# mainboard_2l.net
KiCad netlist of a schematic drawn in EAGLE
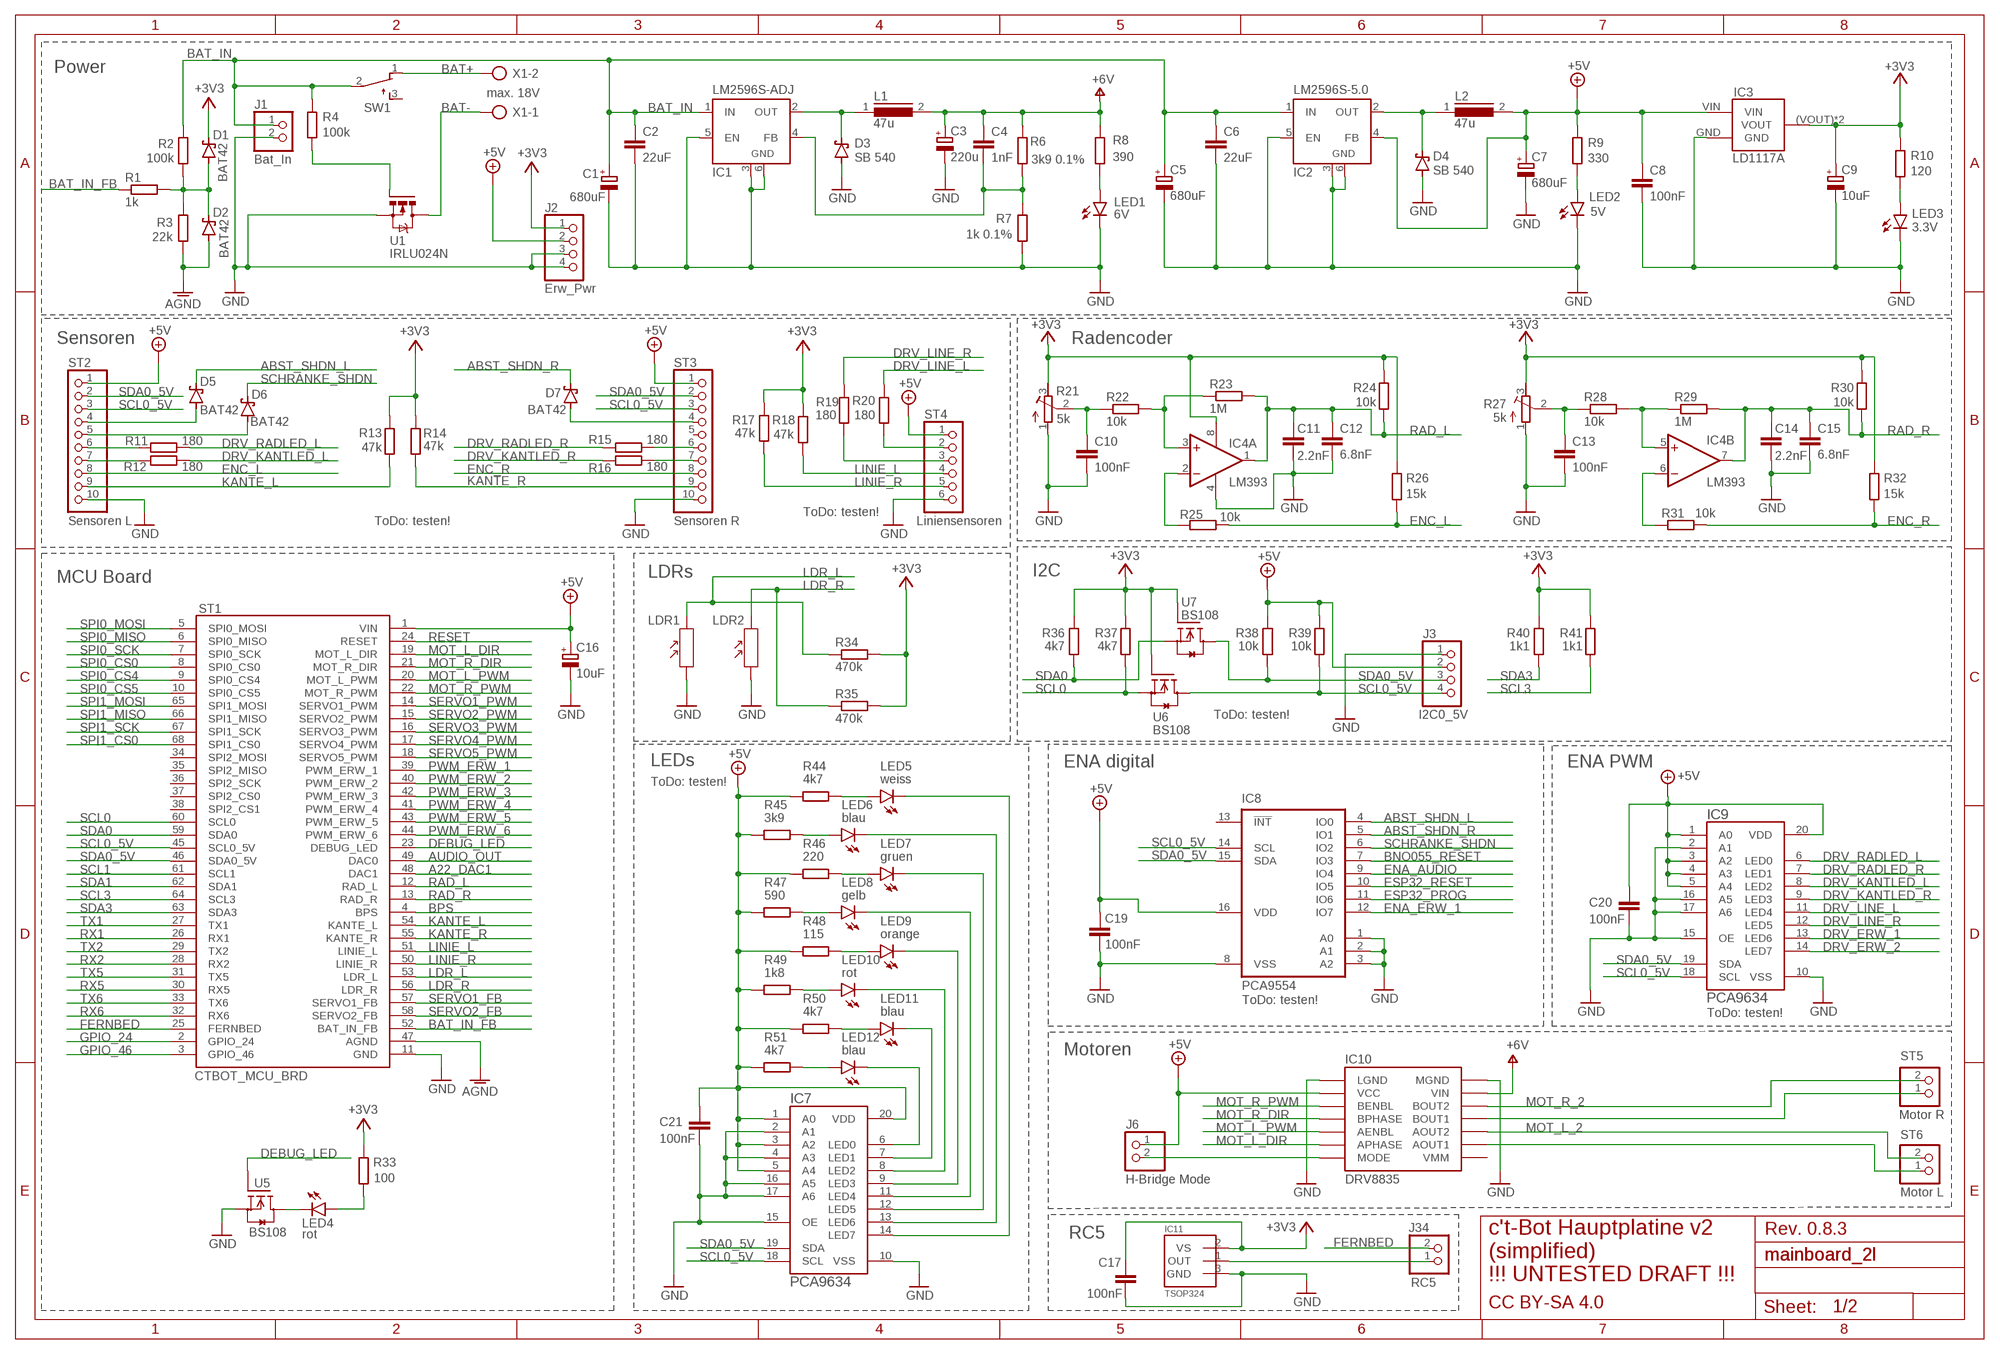
[diagram p0: schematic, sheet 1]
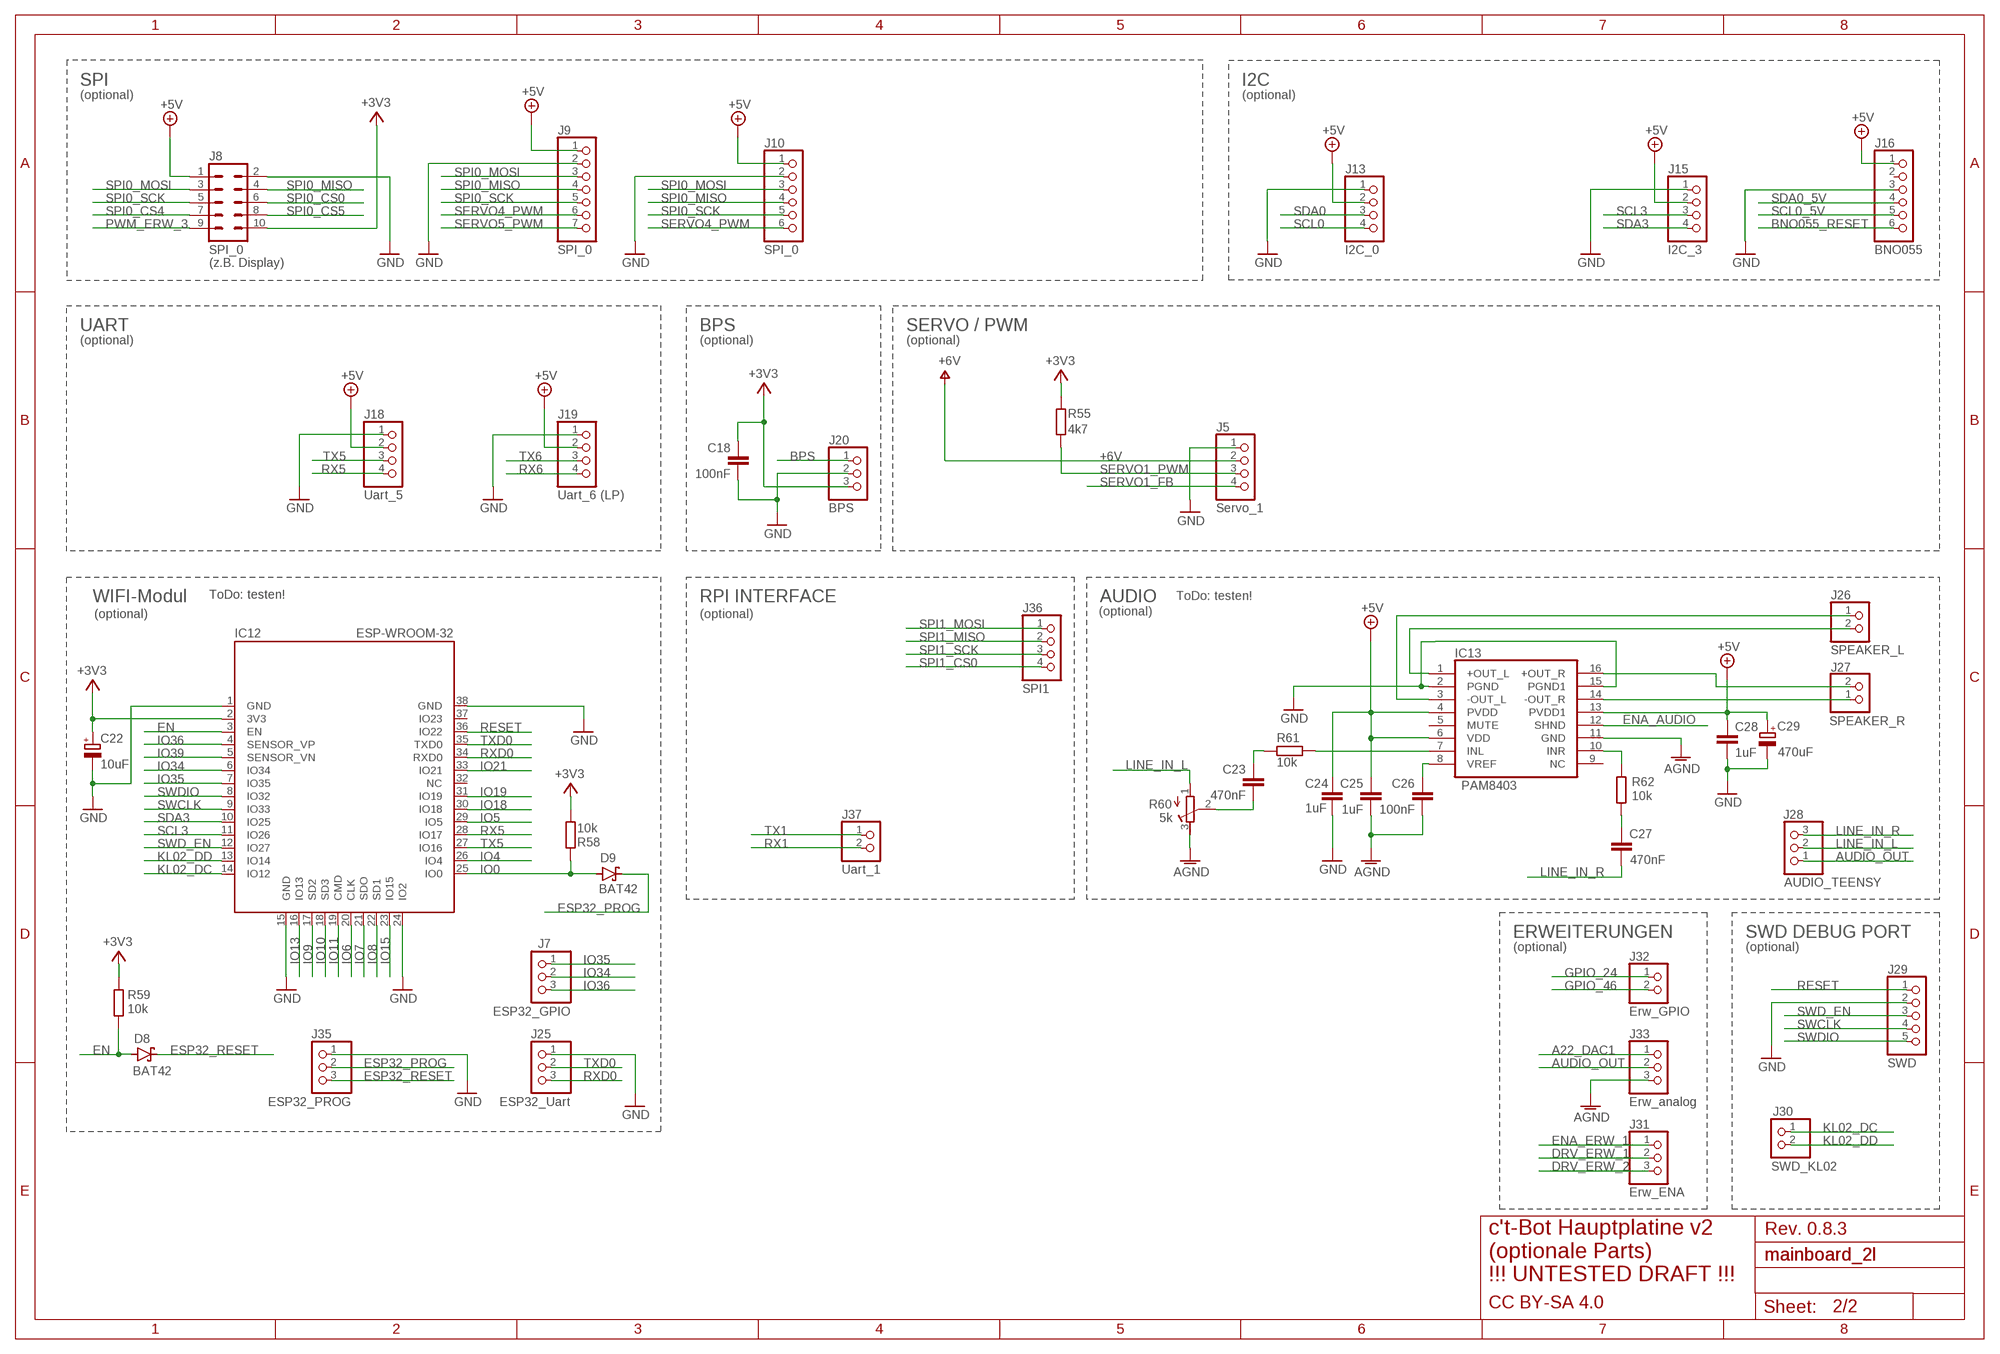
[diagram p1: schematic, sheet 2]

(export (version "E")
  (design (tool "Eeschema 10.0.6"))
  (components
    (comp (ref "C1")
      (value "680uF")
      (footprint "eagle-import:E5-10,5")
      (libsource (lib "eagle-import") (part "CPOL-EUE5-10.5"))
    )
    (comp (ref "C2")
      (value "22uF")
      (footprint "eagle-import:C025-025X050")
      (libsource (lib "eagle-import") (part "C-EU025-025X050"))
    )
    (comp (ref "C3")
      (value "220u")
      (footprint "eagle-import:E5-10,5")
      (libsource (lib "eagle-import") (part "CPOL-EUE5-10.5"))
    )
    (comp (ref "C4")
      (value "1nF")
      (footprint "eagle-import:C025-025X050")
      (libsource (lib "eagle-import") (part "C-EU025-025X050"))
    )
    (comp (ref "C5")
      (value "680uF")
      (footprint "eagle-import:E5-10,5")
      (libsource (lib "eagle-import") (part "CPOL-EUE5-10.5"))
    )
    (comp (ref "C6")
      (value "22uF")
      (footprint "eagle-import:C025-025X050")
      (libsource (lib "eagle-import") (part "C-EU025-025X050"))
    )
    (comp (ref "C7")
      (value "680uF")
      (footprint "eagle-import:E5-10,5")
      (libsource (lib "eagle-import") (part "CPOL-EUE5-10.5"))
    )
    (comp (ref "C8")
      (value "100nF")
      (footprint "eagle-import:C025-025X050")
      (libsource (lib "eagle-import") (part "C-EU025-025X050"))
    )
    (comp (ref "C9")
      (value "10uF")
      (footprint "eagle-import:E2-5")
      (libsource (lib "eagle-import") (part "CPOL-EUE2-5"))
    )
    (comp (ref "C10")
      (value "100nF")
      (footprint "eagle-import:C025-025X050")
      (libsource (lib "eagle-import") (part "C-EU025-025X050"))
    )
    (comp (ref "C11")
      (value "2.2nF")
      (footprint "eagle-import:C025-025X050")
      (libsource (lib "eagle-import") (part "C-EU025-025X050"))
    )
    (comp (ref "C12")
      (value "6.8nF")
      (footprint "eagle-import:C025-025X050")
      (libsource (lib "eagle-import") (part "C-EU025-025X050"))
    )
    (comp (ref "C13")
      (value "100nF")
      (footprint "eagle-import:C025-025X050")
      (libsource (lib "eagle-import") (part "C-EU025-025X050"))
    )
    (comp (ref "C14")
      (value "2.2nF")
      (footprint "eagle-import:C025-025X050")
      (libsource (lib "eagle-import") (part "C-EU025-025X050"))
    )
    (comp (ref "C15")
      (value "6.8nF")
      (footprint "eagle-import:C025-025X050")
      (libsource (lib "eagle-import") (part "C-EU025-025X050"))
    )
    (comp (ref "C16")
      (value "10uF")
      (footprint "eagle-import:TT2D5L")
      (libsource (lib "eagle-import") (part "CPOL-EUTT2D5L"))
    )
    (comp (ref "C17")
      (value "100nF")
      (footprint "eagle-import:C025-025X050")
      (libsource (lib "eagle-import") (part "C-EU025-025X050"))
    )
    (comp (ref "C19")
      (value "100nF")
      (footprint "eagle-import:C025-025X050")
      (libsource (lib "eagle-import") (part "C-EU025-025X050"))
    )
    (comp (ref "C20")
      (value "100nF")
      (footprint "eagle-import:C025-025X050")
      (libsource (lib "eagle-import") (part "C-EU025-025X050"))
    )
    (comp (ref "C21")
      (value "100nF")
      (footprint "eagle-import:C025-025X050")
      (libsource (lib "eagle-import") (part "C-EU025-025X050"))
    )
    (comp (ref "D1")
      (value "BAT42")
      (footprint "eagle-import:DO35-7")
      (libsource (lib "eagle-import") (part "BAT42DO35-7"))
    )
    (comp (ref "D2")
      (value "BAT42")
      (footprint "eagle-import:DO35-7")
      (libsource (lib "eagle-import") (part "BAT42DO35-7"))
    )
    (comp (ref "D3")
      (value "SB 540")
      (footprint "eagle-import:DO201T15")
      (libsource (lib "eagle-import") (part "SCHOTTKY-DIODEDO201T15"))
    )
    (comp (ref "D4")
      (value "SB 540")
      (footprint "eagle-import:DO201T15")
      (libsource (lib "eagle-import") (part "SCHOTTKY-DIODEDO201T15"))
    )
    (comp (ref "D5")
      (value "BAT42")
      (footprint "eagle-import:0207_2V")
      (libsource (lib "eagle-import") (part "BAT42{dblquote}"))
    )
    (comp (ref "D6")
      (value "BAT42")
      (footprint "eagle-import:0207_2V")
      (libsource (lib "eagle-import") (part "BAT42{dblquote}"))
    )
    (comp (ref "D7")
      (value "BAT42")
      (footprint "eagle-import:0207_2V")
      (libsource (lib "eagle-import") (part "BAT42{dblquote}"))
    )
    (comp (ref "IC1")
      (value "LM2596S-ADJ")
      (footprint "eagle-import:TO263-5")
      (libsource (lib "eagle-import") (part "LM2596S"))
    )
    (comp (ref "IC2")
      (value "LM2596S-5.0")
      (footprint "eagle-import:TO263-5")
      (libsource (lib "eagle-import") (part "LM2596S"))
    )
    (comp (ref "IC3")
      (value "LD1117A")
      (footprint "eagle-import:LD1117SOT-223")
      (libsource (lib "eagle-import") (part "LD1117"))
    )
    (comp (ref "IC4")
      (value "LM393")
      (footprint "eagle-import:DIL08")
      (fields (field (name "SPICEPREFIX") "J"))
      (libsource (lib "eagle-import") (part "LM393N"))
    )
    (comp (ref "IC7")
      (value "PCA9634")
      (footprint "eagle-import:SO20W")
      (libsource (lib "eagle-import") (part "PCA9634-SO20"))
    )
    (comp (ref "IC8")
      (value "PCA9554")
      (footprint "eagle-import:SO16W")
      (libsource (lib "eagle-import") (part "PCA9554D"))
    )
    (comp (ref "IC9")
      (value "PCA9634")
      (footprint "eagle-import:SO20W")
      (libsource (lib "eagle-import") (part "PCA9634-SO20"))
    )
    (comp (ref "IC10")
      (value "DRV8835")
      (footprint "eagle-import:DRV8835")
      (libsource (lib "eagle-import") (part "DRV8835THROUGHHOLE"))
    )
    (comp (ref "IC11")
      (value "TSOP324")
      (footprint "eagle-import:TSOP324")
      (libsource (lib "eagle-import") (part "TSOP324"))
    )
    (comp (ref "J1")
      (value "Bat_In")
      (footprint "eagle-import:1X02")
      (libsource (lib "eagle-import") (part "PINHD-1X2"))
    )
    (comp (ref "J2")
      (value "Erw_Pwr")
      (footprint "eagle-import:1X04")
      (libsource (lib "eagle-import") (part "PINHD-1X4"))
    )
    (comp (ref "J3")
      (value "I2C0_5V")
      (footprint "eagle-import:1X04")
      (libsource (lib "eagle-import") (part "PINHD-1X4"))
    )
    (comp (ref "J6")
      (value "H-Bridge Mode")
      (footprint "eagle-import:1X02")
      (libsource (lib "eagle-import") (part "PINHD-1X2"))
    )
    (comp (ref "J34")
      (value "RC5")
      (footprint "eagle-import:1X02")
      (libsource (lib "eagle-import") (part "PINHD-1X2"))
    )
    (comp (ref "L1")
      (value "47u")
      (footprint "eagle-import:09HCP")
      (libsource (lib "eagle-import") (part "INDUCTOR_09HCP"))
    )
    (comp (ref "L2")
      (value "47u")
      (footprint "eagle-import:09HCP")
      (libsource (lib "eagle-import") (part "INDUCTOR_09HCP"))
    )
    (comp (ref "LDR1")
      (value "MPY54C569")
      (footprint "eagle-import:SNR2-3.0")
      (fields (field (name "MPN") "PHOTORESISTOR-5528-10K"))
      (libsource (lib "eagle-import") (part "MPY54C569"))
    )
    (comp (ref "LDR2")
      (value "MPY54C569")
      (footprint "eagle-import:SNR2-3.0")
      (fields (field (name "MPN") "PHOTORESISTOR-5528-10K"))
      (libsource (lib "eagle-import") (part "MPY54C569"))
    )
    (comp (ref "LED1")
      (value "6V")
      (footprint "eagle-import:LED3MM")
      (libsource (lib "eagle-import") (part "LED3MM"))
    )
    (comp (ref "LED2")
      (value "5V")
      (footprint "eagle-import:LED3MM")
      (libsource (lib "eagle-import") (part "LED3MM"))
    )
    (comp (ref "LED3")
      (value "3.3V")
      (footprint "eagle-import:LED3MM")
      (libsource (lib "eagle-import") (part "LED3MM"))
    )
    (comp (ref "LED4")
      (value "rot")
      (footprint "eagle-import:LED3MM")
      (libsource (lib "eagle-import") (part "LED3MM"))
    )
    (comp (ref "LED5")
      (value "weiss")
      (footprint "eagle-import:LED3MM")
      (libsource (lib "eagle-import") (part "LED3MM"))
    )
    (comp (ref "LED6")
      (value "blau")
      (footprint "eagle-import:LED3MM")
      (libsource (lib "eagle-import") (part "LED3MM"))
    )
    (comp (ref "LED7")
      (value "gruen")
      (footprint "eagle-import:LED3MM")
      (libsource (lib "eagle-import") (part "LED3MM"))
    )
    (comp (ref "LED8")
      (value "gelb")
      (footprint "eagle-import:LED3MM")
      (libsource (lib "eagle-import") (part "LED3MM"))
    )
    (comp (ref "LED9")
      (value "orange")
      (footprint "eagle-import:LED3MM")
      (libsource (lib "eagle-import") (part "LED3MM"))
    )
    (comp (ref "LED10")
      (value "rot")
      (footprint "eagle-import:LED3MM")
      (libsource (lib "eagle-import") (part "LED3MM"))
    )
    (comp (ref "LED11")
      (value "blau")
      (footprint "eagle-import:LED3MM")
      (libsource (lib "eagle-import") (part "LED3MM"))
    )
    (comp (ref "LED12")
      (value "blau")
      (footprint "eagle-import:LED3MM")
      (libsource (lib "eagle-import") (part "LED3MM"))
    )
    (comp (ref "R1")
      (value "1k")
      (footprint "eagle-import:0204_7")
      (libsource (lib "eagle-import") (part "R-EU_0204/7"))
    )
    (comp (ref "R2")
      (value "100k")
      (footprint "eagle-import:0204V")
      (libsource (lib "eagle-import") (part "R-EU_0204/2V"))
    )
    (comp (ref "R3")
      (value "22k")
      (footprint "eagle-import:0204_7")
      (libsource (lib "eagle-import") (part "R-EU_0204/7"))
    )
    (comp (ref "R4")
      (value "100k")
      (footprint "eagle-import:0204V")
      (libsource (lib "eagle-import") (part "R-EU_0204/2V"))
    )
    (comp (ref "R6")
      (value "3k9 0.1%")
      (footprint "eagle-import:0204V")
      (libsource (lib "eagle-import") (part "R-EU_0204/2V"))
    )
    (comp (ref "R7")
      (value "1k 0.1%")
      (footprint "eagle-import:0204V")
      (libsource (lib "eagle-import") (part "R-EU_0204/2V"))
    )
    (comp (ref "R8")
      (value "390")
      (footprint "eagle-import:0204V")
      (libsource (lib "eagle-import") (part "R-EU_0204/2V"))
    )
    (comp (ref "R9")
      (value "330")
      (footprint "eagle-import:0204V")
      (libsource (lib "eagle-import") (part "R-EU_0204/2V"))
    )
    (comp (ref "R10")
      (value "120")
      (footprint "eagle-import:0204V")
      (libsource (lib "eagle-import") (part "R-EU_0204/2V"))
    )
    (comp (ref "R11")
      (value "180")
      (footprint "eagle-import:0204V")
      (libsource (lib "eagle-import") (part "R-EU_0204/2V"))
    )
    (comp (ref "R12")
      (value "180")
      (footprint "eagle-import:0204V")
      (libsource (lib "eagle-import") (part "R-EU_0204/2V"))
    )
    (comp (ref "R13")
      (value "47k")
      (footprint "eagle-import:0204V")
      (libsource (lib "eagle-import") (part "R-EU_0204/2V"))
    )
    (comp (ref "R14")
      (value "47k")
      (footprint "eagle-import:0204V")
      (libsource (lib "eagle-import") (part "R-EU_0204/2V"))
    )
    (comp (ref "R15")
      (value "180")
      (footprint "eagle-import:0204V")
      (libsource (lib "eagle-import") (part "R-EU_0204/2V"))
    )
    (comp (ref "R16")
      (value "180")
      (footprint "eagle-import:0204V")
      (libsource (lib "eagle-import") (part "R-EU_0204/2V"))
    )
    (comp (ref "R17")
      (value "47k")
      (footprint "eagle-import:0204V")
      (libsource (lib "eagle-import") (part "R-EU_0204/2V"))
    )
    (comp (ref "R18")
      (value "47k")
      (footprint "eagle-import:0204V")
      (libsource (lib "eagle-import") (part "R-EU_0204/2V"))
    )
    (comp (ref "R19")
      (value "180")
      (footprint "eagle-import:0204V")
      (libsource (lib "eagle-import") (part "R-EU_0204/2V"))
    )
    (comp (ref "R20")
      (value "180")
      (footprint "eagle-import:0204V")
      (libsource (lib "eagle-import") (part "R-EU_0204/2V"))
    )
    (comp (ref "R21")
      (value "5k")
      (footprint "eagle-import:RTRIM64W")
      (libsource (lib "eagle-import") (part "R-TRIMM64W"))
    )
    (comp (ref "R22")
      (value "10k")
      (footprint "eagle-import:0204V")
      (libsource (lib "eagle-import") (part "R-EU_0204/2V"))
    )
    (comp (ref "R23")
      (value "1M")
      (footprint "eagle-import:0204V")
      (libsource (lib "eagle-import") (part "R-EU_0204/2V"))
    )
    (comp (ref "R24")
      (value "10k")
      (footprint "eagle-import:0204V")
      (libsource (lib "eagle-import") (part "R-EU_0204/2V"))
    )
    (comp (ref "R25")
      (value "10k")
      (footprint "eagle-import:0204V")
      (libsource (lib "eagle-import") (part "R-EU_0204/2V"))
    )
    (comp (ref "R26")
      (value "15k")
      (footprint "eagle-import:0204V")
      (libsource (lib "eagle-import") (part "R-EU_0204/2V"))
    )
    (comp (ref "R27")
      (value "5k")
      (footprint "eagle-import:RTRIM64W")
      (libsource (lib "eagle-import") (part "R-TRIMM64W"))
    )
    (comp (ref "R28")
      (value "10k")
      (footprint "eagle-import:0204_7")
      (libsource (lib "eagle-import") (part "R-EU_0204/7"))
    )
    (comp (ref "R29")
      (value "1M")
      (footprint "eagle-import:0204_7")
      (libsource (lib "eagle-import") (part "R-EU_0204/7"))
    )
    (comp (ref "R30")
      (value "10k")
      (footprint "eagle-import:0204_7")
      (libsource (lib "eagle-import") (part "R-EU_0204/7"))
    )
    (comp (ref "R31")
      (value "10k")
      (footprint "eagle-import:0204V")
      (libsource (lib "eagle-import") (part "R-EU_0204/2V"))
    )
    (comp (ref "R32")
      (value "15k")
      (footprint "eagle-import:0204V")
      (libsource (lib "eagle-import") (part "R-EU_0204/2V"))
    )
    (comp (ref "R33")
      (value "100")
      (footprint "eagle-import:0204V")
      (libsource (lib "eagle-import") (part "R-EU_0204/2V"))
    )
    (comp (ref "R34")
      (value "470k")
      (footprint "eagle-import:0204V")
      (libsource (lib "eagle-import") (part "R-EU_0204/2V"))
    )
    (comp (ref "R35")
      (value "470k")
      (footprint "eagle-import:0204V")
      (libsource (lib "eagle-import") (part "R-EU_0204/2V"))
    )
    (comp (ref "R36")
      (value "4k7")
      (footprint "eagle-import:0204V")
      (libsource (lib "eagle-import") (part "R-EU_0204/2V"))
    )
    (comp (ref "R37")
      (value "4k7")
      (footprint "eagle-import:0204V")
      (libsource (lib "eagle-import") (part "R-EU_0204/2V"))
    )
    (comp (ref "R38")
      (value "10k")
      (footprint "eagle-import:0204V")
      (libsource (lib "eagle-import") (part "R-EU_0204/2V"))
    )
    (comp (ref "R39")
      (value "10k")
      (footprint "eagle-import:0204V")
      (libsource (lib "eagle-import") (part "R-EU_0204/2V"))
    )
    (comp (ref "R40")
      (value "1k1")
      (footprint "eagle-import:0204V")
      (libsource (lib "eagle-import") (part "R-EU_0204/2V"))
    )
    (comp (ref "R41")
      (value "1k1")
      (footprint "eagle-import:0204V")
      (libsource (lib "eagle-import") (part "R-EU_0204/2V"))
    )
    (comp (ref "R44")
      (value "4k7")
      (footprint "eagle-import:0204V")
      (libsource (lib "eagle-import") (part "R-EU_0204/2V"))
    )
    (comp (ref "R45")
      (value "3k9")
      (footprint "eagle-import:0204V")
      (libsource (lib "eagle-import") (part "R-EU_0204/2V"))
    )
    (comp (ref "R46")
      (value "220")
      (footprint "eagle-import:0204V")
      (libsource (lib "eagle-import") (part "R-EU_0204/2V"))
    )
    (comp (ref "R47")
      (value "590")
      (footprint "eagle-import:0204V")
      (libsource (lib "eagle-import") (part "R-EU_0204/2V"))
    )
    (comp (ref "R48")
      (value "115")
      (footprint "eagle-import:0204V")
      (libsource (lib "eagle-import") (part "R-EU_0204/2V"))
    )
    (comp (ref "R49")
      (value "1k8")
      (footprint "eagle-import:0204V")
      (libsource (lib "eagle-import") (part "R-EU_0204/2V"))
    )
    (comp (ref "R50")
      (value "4k7")
      (footprint "eagle-import:0204V")
      (libsource (lib "eagle-import") (part "R-EU_0204/2V"))
    )
    (comp (ref "R51")
      (value "4k7")
      (footprint "eagle-import:0204V")
      (libsource (lib "eagle-import") (part "R-EU_0204/2V"))
    )
    (comp (ref "ST1")
      (value "CTBOT_MCU_BRD")
      (footprint "eagle-import:DIP66")
      (libsource (lib "eagle-import") (part "CTBOT_MCU_BRD"))
    )
    (comp (ref "ST2")
      (value "Sensoren L")
      (footprint "eagle-import:TS_PS25_10")
      (libsource (lib "eagle-import") (part "PS25-10PS25-10"))
    )
    (comp (ref "ST3")
      (value "Sensoren R")
      (footprint "eagle-import:TS_PS25_10")
      (libsource (lib "eagle-import") (part "PS25-10PS25-10"))
    )
    (comp (ref "ST4")
      (value "Liniensensoren")
      (footprint "eagle-import:TS_PS25_6")
      (libsource (lib "eagle-import") (part "PS25-6"))
    )
    (comp (ref "ST5")
      (value "Motor R")
      (footprint "eagle-import:1X02_90")
      (libsource (lib "eagle-import") (part "PINHD90-1X2/90"))
    )
    (comp (ref "ST6")
      (value "Motor L")
      (footprint "eagle-import:1X02_90")
      (libsource (lib "eagle-import") (part "PINHD90-1X2/90"))
    )
    (comp (ref "SW1")
      (value "TL32PO")
      (footprint "eagle-import:TL3XPO")
      (libsource (lib "eagle-import") (part "TL32PO"))
    )
    (comp (ref "U1")
      (value "IRLU024N")
      (footprint "eagle-import:TO251AA")
      (libsource (lib "eagle-import") (part "IRLU024NTO-251AA"))
    )
    (comp (ref "U5")
      (value "BS108")
      (footprint "eagle-import:SOT54E")
      (libsource (lib "eagle-import") (part "BS108"))
    )
    (comp (ref "U6")
      (value "BS108")
      (footprint "eagle-import:SOT54E")
      (libsource (lib "eagle-import") (part "BS108"))
    )
    (comp (ref "U7")
      (value "BS108")
      (footprint "eagle-import:SOT54E")
      (libsource (lib "eagle-import") (part "BS108"))
    )
    (comp (ref "X1")
      (value "max. 18V")
      (footprint "eagle-import:AK500_2-H")
      (libsource (lib "eagle-import") (part "SCHRAUBKLEMME/2"))
    )
    (comp (ref "C18")
      (value "100nF")
      (footprint "eagle-import:C025-025X050")
      (libsource (lib "eagle-import") (part "C-EU025-025X050"))
    )
    (comp (ref "C22")
      (value "10uF")
      (footprint "eagle-import:E2,5-5")
      (libsource (lib "eagle-import") (part "CPOL-EUE2.5-5"))
    )
    (comp (ref "C23")
      (value "470nF")
      (footprint "eagle-import:C025-025X050")
      (libsource (lib "eagle-import") (part "C-EU025-025X050"))
    )
    (comp (ref "C24")
      (value "1uF")
      (footprint "eagle-import:C025-025X050")
      (libsource (lib "eagle-import") (part "C-EU025-025X050"))
    )
    (comp (ref "C25")
      (value "1uF")
      (footprint "eagle-import:C025-025X050")
      (libsource (lib "eagle-import") (part "C-EU025-025X050"))
    )
    (comp (ref "C26")
      (value "100nF")
      (footprint "eagle-import:C025-025X050")
      (libsource (lib "eagle-import") (part "C-EU025-025X050"))
    )
    (comp (ref "C27")
      (value "470nF")
      (footprint "eagle-import:C025-025X050")
      (libsource (lib "eagle-import") (part "C-EU025-025X050"))
    )
    (comp (ref "C28")
      (value "1uF")
      (footprint "eagle-import:C025-025X050")
      (libsource (lib "eagle-import") (part "C-EU025-025X050"))
    )
    (comp (ref "C29")
      (value "470uF")
      (footprint "eagle-import:E3,5-8")
      (libsource (lib "eagle-import") (part "CPOL-EUE3.5-8"))
    )
    (comp (ref "D8")
      (value "BAT42")
      (footprint "eagle-import:0207_2V")
      (libsource (lib "eagle-import") (part "BAT42{dblquote}"))
    )
    (comp (ref "D9")
      (value "BAT42")
      (footprint "eagle-import:0207_2V")
      (libsource (lib "eagle-import") (part "BAT42{dblquote}"))
    )
    (comp (ref "IC12")
      (value "ESP-WROOM-32")
      (footprint "eagle-import:ESP-WROOM-32")
      (libsource (lib "eagle-import") (part "ESP-WROOM-32"))
    )
    (comp (ref "IC13")
      (value "PAM8403")
      (footprint "eagle-import:SOP-16")
      (libsource (lib "eagle-import") (part "PAM8403"))
    )
    (comp (ref "J5")
      (value "Servo_1")
      (footprint "eagle-import:1X04")
      (libsource (lib "eagle-import") (part "PINHD-1X4"))
    )
    (comp (ref "J7")
      (value "ESP32_GPIO")
      (footprint "eagle-import:1X03")
      (fields (field (name "SPICEPREFIX") "J"))
      (libsource (lib "eagle-import") (part "PINHD-1X3"))
    )
    (comp (ref "J8")
      (value "SPI_0")
      (footprint "eagle-import:ML10")
      (libsource (lib "eagle-import") (part "ML10"))
    )
    (comp (ref "J9")
      (value "SPI_0")
      (footprint "eagle-import:1X07")
      (libsource (lib "eagle-import") (part "PINHD-1X7"))
    )
    (comp (ref "J10")
      (value "SPI_0")
      (footprint "eagle-import:1X06")
      (libsource (lib "eagle-import") (part "PINHD-1X6"))
    )
    (comp (ref "J13")
      (value "I2C_0")
      (footprint "eagle-import:1X04")
      (libsource (lib "eagle-import") (part "PINHD-1X4"))
    )
    (comp (ref "J15")
      (value "I2C_3")
      (footprint "eagle-import:1X04")
      (libsource (lib "eagle-import") (part "PINHD-1X4"))
    )
    (comp (ref "J16")
      (value "BNO055")
      (footprint "eagle-import:1X06")
      (libsource (lib "eagle-import") (part "PINHD-1X6"))
    )
    (comp (ref "J18")
      (value "Uart_5")
      (footprint "eagle-import:1X04")
      (libsource (lib "eagle-import") (part "PINHD-1X4"))
    )
    (comp (ref "J19")
      (value "Uart_6 (LP)")
      (footprint "eagle-import:1X04")
      (libsource (lib "eagle-import") (part "PINHD-1X4"))
    )
    (comp (ref "J20")
      (value "BPS")
      (footprint "eagle-import:1X03")
      (libsource (lib "eagle-import") (part "PINHD-1X3"))
    )
    (comp (ref "J25")
      (value "ESP32_Uart")
      (footprint "eagle-import:1X03")
      (fields (field (name "SPICEPREFIX") "J"))
      (libsource (lib "eagle-import") (part "PINHD-1X3"))
    )
    (comp (ref "J26")
      (value "SPEAKER_L")
      (footprint "eagle-import:1X02")
      (libsource (lib "eagle-import") (part "PINHD-1X2"))
    )
    (comp (ref "J27")
      (value "SPEAKER_R")
      (footprint "eagle-import:1X02")
      (libsource (lib "eagle-import") (part "PINHD-1X2"))
    )
    (comp (ref "J28")
      (value "AUDIO_TEENSY")
      (footprint "eagle-import:1X03")
      (libsource (lib "eagle-import") (part "PINHD-1X3"))
    )
    (comp (ref "J29")
      (value "SWD")
      (footprint "eagle-import:1X05")
      (libsource (lib "eagle-import") (part "PINHD-1X5"))
    )
    (comp (ref "J30")
      (value "SWD_KL02")
      (footprint "eagle-import:1X02")
      (libsource (lib "eagle-import") (part "PINHD-1X2"))
    )
    (comp (ref "J31")
      (value "Erw_ENA")
      (footprint "eagle-import:1X03")
      (libsource (lib "eagle-import") (part "PINHD-1X3"))
    )
    (comp (ref "J32")
      (value "Erw_GPIO")
      (footprint "eagle-import:1X02")
      (libsource (lib "eagle-import") (part "PINHD-1X2"))
    )
    (comp (ref "J33")
      (value "Erw_analog")
      (footprint "eagle-import:1X03")
      (libsource (lib "eagle-import") (part "PINHD-1X3"))
    )
    (comp (ref "J35")
      (value "ESP32_PROG")
      (footprint "eagle-import:1X03")
      (libsource (lib "eagle-import") (part "PINHD-1X3"))
    )
    (comp (ref "J36")
      (value "SPI1")
      (footprint "eagle-import:1X04")
      (libsource (lib "eagle-import") (part "PINHD-1X4"))
    )
    (comp (ref "J37")
      (value "Uart_1")
      (footprint "eagle-import:1X02")
      (libsource (lib "eagle-import") (part "PINHD-1X2"))
    )
    (comp (ref "R55")
      (value "4k7")
      (footprint "eagle-import:0204_7")
      (libsource (lib "eagle-import") (part "R-EU_0204/7"))
    )
    (comp (ref "R58")
      (value "10k")
      (footprint "eagle-import:0204V")
      (libsource (lib "eagle-import") (part "R-EU_0204/2V"))
    )
    (comp (ref "R59")
      (value "10k")
      (footprint "eagle-import:0204V")
      (libsource (lib "eagle-import") (part "R-EU_0204/2V"))
    )
    (comp (ref "R60")
      (value "5k")
      (footprint "eagle-import:RTRIM64W")
      (libsource (lib "eagle-import") (part "R-TRIMM64W"))
    )
    (comp (ref "R61")
      (value "10k")
      (footprint "eagle-import:0204V")
      (libsource (lib "eagle-import") (part "R-EU_0204/2V"))
    )
    (comp (ref "R62")
      (value "10k")
      (footprint "eagle-import:0204V")
      (libsource (lib "eagle-import") (part "R-EU_0204/2V"))
    )
  )
  (nets
    (net (code "1") (name "+3V3") (class "Default")
      (node (ref "C17") (pin "1") (pinfunction "1_1") (pintype "passive"))
      (node (ref "C18") (pin "1") (pinfunction "1_1") (pintype "passive"))
      (node (ref "C22") (pin "+") (pinfunction "+_+") (pintype "passive"))
      (node (ref "C9") (pin "+") (pinfunction "+_+") (pintype "passive"))
      (node (ref "D1") (pin "C") (pinfunction "C_C") (pintype "passive"))
      (node (ref "IC11") (pin "2") (pinfunction "VS_2") (pintype "power_in"))
      (node (ref "IC12") (pin "2") (pinfunction "3V3_2") (pintype "bidirectional"))
      (node (ref "IC3") (pin "(VOUT)") (pinfunction "VOUT_(VOUT)") (pintype "bidirectional"))
      (node (ref "IC3") (pin "VOUT") (pinfunction "VOUT_VOUT") (pintype "bidirectional"))
      (node (ref "IC4") (pin "8") (pinfunction "V+_8") (pintype "power_in"))
      (node (ref "J2") (pin "1") (pinfunction "1_1") (pintype "passive"))
      (node (ref "J20") (pin "3") (pinfunction "3_3") (pintype "passive"))
      (node (ref "J8") (pin "10") (pinfunction "10_10") (pintype "passive"))
      (node (ref "R10") (pin "2") (pinfunction "2_2") (pintype "passive"))
      (node (ref "R13") (pin "2") (pinfunction "2_2") (pintype "passive"))
      (node (ref "R14") (pin "1") (pinfunction "1_1") (pintype "passive"))
      (node (ref "R17") (pin "2") (pinfunction "2_2") (pintype "passive"))
      (node (ref "R18") (pin "2") (pinfunction "2_2") (pintype "passive"))
      (node (ref "R21") (pin "3") (pinfunction "E_3") (pintype "passive"))
      (node (ref "R24") (pin "2") (pinfunction "2_2") (pintype "passive"))
      (node (ref "R26") (pin "2") (pinfunction "2_2") (pintype "passive"))
      (node (ref "R27") (pin "3") (pinfunction "E_3") (pintype "passive"))
      (node (ref "R30") (pin "2") (pinfunction "2_2") (pintype "passive"))
      (node (ref "R32") (pin "2") (pinfunction "2_2") (pintype "passive"))
      (node (ref "R33") (pin "2") (pinfunction "2_2") (pintype "passive"))
      (node (ref "R34") (pin "2") (pinfunction "2_2") (pintype "passive"))
      (node (ref "R35") (pin "2") (pinfunction "2_2") (pintype "passive"))
      (node (ref "R36") (pin "2") (pinfunction "2_2") (pintype "passive"))
      (node (ref "R37") (pin "2") (pinfunction "2_2") (pintype "passive"))
      (node (ref "R40") (pin "2") (pinfunction "2_2") (pintype "passive"))
      (node (ref "R41") (pin "2") (pinfunction "2_2") (pintype "passive"))
      (node (ref "R55") (pin "2") (pinfunction "2_2") (pintype "passive"))
      (node (ref "R58") (pin "1") (pinfunction "1_1") (pintype "passive"))
      (node (ref "R59") (pin "2") (pinfunction "2_2") (pintype "passive"))
      (node (ref "U6") (pin "G") (pinfunction "G_G") (pintype "passive"))
      (node (ref "U7") (pin "G") (pinfunction "G_G") (pintype "passive"))
    )
    (net (code "2") (name "+5V") (class "Default")
      (node (ref "C16") (pin "+") (pinfunction "+_+") (pintype "passive"))
      (node (ref "C19") (pin "1") (pinfunction "1_1") (pintype "passive"))
      (node (ref "C20") (pin "1") (pinfunction "1_1") (pintype "passive"))
      (node (ref "C21") (pin "1") (pinfunction "1_1") (pintype "passive"))
      (node (ref "C24") (pin "1") (pinfunction "1_1") (pintype "passive"))
      (node (ref "C25") (pin "1") (pinfunction "1_1") (pintype "passive"))
      (node (ref "C28") (pin "1") (pinfunction "1_1") (pintype "passive"))
      (node (ref "C29") (pin "+") (pinfunction "+_+") (pintype "passive"))
      (node (ref "C7") (pin "+") (pinfunction "+_+") (pintype "passive"))
      (node (ref "C8") (pin "1") (pinfunction "1_1") (pintype "passive"))
      (node (ref "IC10") (pin "VCC") (pinfunction "VCC_VCC") (pintype "bidirectional"))
      (node (ref "IC13") (pin "13") (pinfunction "PVDD1_13") (pintype "power_in"))
      (node (ref "IC13") (pin "4") (pinfunction "PVDD_4") (pintype "power_in"))
      (node (ref "IC13") (pin "6") (pinfunction "VDD_6") (pintype "power_in"))
      (node (ref "IC2") (pin "4") (pinfunction "FB_4") (pintype "input"))
      (node (ref "IC3") (pin "VIN") (pinfunction "VIN_VIN") (pintype "bidirectional"))
      (node (ref "IC7") (pin "1") (pinfunction "A0_1") (pintype "input"))
      (node (ref "IC7") (pin "20") (pinfunction "VDD_20") (pintype "power_in"))
      (node (ref "IC7") (pin "3") (pinfunction "A2_3") (pintype "input"))
      (node (ref "IC7") (pin "5") (pinfunction "A4_5") (pintype "input"))
      (node (ref "IC8") (pin "16") (pinfunction "VDD_16") (pintype "power_in"))
      (node (ref "IC9") (pin "1") (pinfunction "A0_1") (pintype "input"))
      (node (ref "IC9") (pin "20") (pinfunction "VDD_20") (pintype "power_in"))
      (node (ref "IC9") (pin "3") (pinfunction "A2_3") (pintype "input"))
      (node (ref "IC9") (pin "4") (pinfunction "A3_4") (pintype "input"))
      (node (ref "IC9") (pin "5") (pinfunction "A4_5") (pintype "input"))
      (node (ref "J10") (pin "1") (pinfunction "1_1") (pintype "passive"))
      (node (ref "J13") (pin "2") (pinfunction "2_2") (pintype "passive"))
      (node (ref "J15") (pin "2") (pinfunction "2_2") (pintype "passive"))
      (node (ref "J16") (pin "1") (pinfunction "1_1") (pintype "passive"))
      (node (ref "J18") (pin "2") (pinfunction "2_2") (pintype "passive"))
      (node (ref "J19") (pin "2") (pinfunction "2_2") (pintype "passive"))
      (node (ref "J2") (pin "2") (pinfunction "2_2") (pintype "passive"))
      (node (ref "J3") (pin "2") (pinfunction "2_2") (pintype "passive"))
      (node (ref "J6") (pin "1") (pinfunction "1_1") (pintype "passive"))
      (node (ref "J8") (pin "1") (pinfunction "1_1") (pintype "passive"))
      (node (ref "J9") (pin "1") (pinfunction "1_1") (pintype "passive"))
      (node (ref "L2") (pin "2") (pinfunction "2_2") (pintype "passive"))
      (node (ref "R38") (pin "2") (pinfunction "2_2") (pintype "passive"))
      (node (ref "R39") (pin "2") (pinfunction "2_2") (pintype "passive"))
      (node (ref "R44") (pin "1") (pinfunction "1_1") (pintype "passive"))
      (node (ref "R45") (pin "1") (pinfunction "1_1") (pintype "passive"))
      (node (ref "R46") (pin "1") (pinfunction "1_1") (pintype "passive"))
      (node (ref "R47") (pin "1") (pinfunction "1_1") (pintype "passive"))
      (node (ref "R48") (pin "1") (pinfunction "1_1") (pintype "passive"))
      (node (ref "R49") (pin "1") (pinfunction "1_1") (pintype "passive"))
      (node (ref "R50") (pin "1") (pinfunction "1_1") (pintype "passive"))
      (node (ref "R51") (pin "1") (pinfunction "1_1") (pintype "passive"))
      (node (ref "R9") (pin "2") (pinfunction "2_2") (pintype "passive"))
      (node (ref "ST1") (pin "1") (pinfunction "VIN_1") (pintype "power_in"))
      (node (ref "ST2") (pin "1") (pinfunction "1_1") (pintype "passive"))
      (node (ref "ST3") (pin "1") (pinfunction "1_1") (pintype "passive"))
      (node (ref "ST4") (pin "1") (pinfunction "1_1") (pintype "passive"))
    )
    (net (code "3") (name "+6V") (class "Default")
      (node (ref "C3") (pin "+") (pinfunction "+_+") (pintype "passive"))
      (node (ref "C4") (pin "1") (pinfunction "1_1") (pintype "passive"))
      (node (ref "IC10") (pin "VIN") (pinfunction "VIN_VIN") (pintype "bidirectional"))
      (node (ref "J5") (pin "2") (pinfunction "2_2") (pintype "passive"))
      (node (ref "L1") (pin "2") (pinfunction "2_2") (pintype "passive"))
      (node (ref "R6") (pin "2") (pinfunction "2_2") (pintype "passive"))
      (node (ref "R8") (pin "1") (pinfunction "1_1") (pintype "passive"))
    )
    (net (code "4") (name "A22_DAC1") (class "Default")
      (node (ref "J33") (pin "1") (pinfunction "1_1") (pintype "passive"))
      (node (ref "ST1") (pin "48") (pinfunction "DAC1_48") (pintype "bidirectional"))
    )
    (net (code "5") (name "ABST_SHDN_L") (class "Default")
      (node (ref "D5") (pin "2") (pinfunction "C_2") (pintype "passive"))
      (node (ref "IC8") (pin "4") (pinfunction "IO0_4") (pintype "bidirectional"))
    )
    (net (code "6") (name "ABST_SHDN_R") (class "Default")
      (node (ref "D7") (pin "2") (pinfunction "C_2") (pintype "passive"))
      (node (ref "IC8") (pin "5") (pinfunction "IO1_5") (pintype "bidirectional"))
    )
    (net (code "7") (name "AGND") (class "Default")
      (node (ref "C25") (pin "2") (pinfunction "2_2") (pintype "passive"))
      (node (ref "C26") (pin "2") (pinfunction "2_2") (pintype "passive"))
      (node (ref "D2") (pin "A") (pinfunction "A_A") (pintype "passive"))
      (node (ref "IC13") (pin "11") (pinfunction "GND_11") (pintype "power_in"))
      (node (ref "J33") (pin "3") (pinfunction "3_3") (pintype "passive"))
      (node (ref "R3") (pin "1") (pinfunction "1_1") (pintype "passive"))
      (node (ref "R60") (pin "3") (pinfunction "E_3") (pintype "passive"))
      (node (ref "ST1") (pin "47") (pinfunction "AGND_47") (pintype "power_in"))
    )
    (net (code "8") (name "AUDIO_OUT") (class "Default")
      (node (ref "J28") (pin "1") (pinfunction "1_1") (pintype "passive"))
      (node (ref "J33") (pin "2") (pinfunction "2_2") (pintype "passive"))
      (node (ref "ST1") (pin "49") (pinfunction "DAC0_49") (pintype "bidirectional"))
    )
    (net (code "9") (name "BAT+") (class "Default")
      (node (ref "SW1") (pin "1") (pinfunction "O_1") (pintype "passive"))
      (node (ref "X1") (pin "2") (pinfunction "KL_2") (pintype "passive"))
    )
    (net (code "10") (name "BAT-") (class "Default")
      (node (ref "U1") (pin "2") (pinfunction "D_2") (pintype "passive"))
      (node (ref "U1") (pin "4") (pinfunction "D_4") (pintype "passive"))
      (node (ref "X1") (pin "1") (pinfunction "KL_1") (pintype "passive"))
    )
    (net (code "11") (name "BAT_IN") (class "Default")
      (node (ref "C1") (pin "+") (pinfunction "+_+") (pintype "passive"))
      (node (ref "C2") (pin "1") (pinfunction "1_1") (pintype "passive"))
      (node (ref "C5") (pin "+") (pinfunction "+_+") (pintype "passive"))
      (node (ref "C6") (pin "1") (pinfunction "1_1") (pintype "passive"))
      (node (ref "IC1") (pin "1") (pinfunction "IN_1") (pintype "input"))
      (node (ref "IC2") (pin "1") (pinfunction "IN_1") (pintype "input"))
      (node (ref "J1") (pin "1") (pinfunction "1_1") (pintype "passive"))
      (node (ref "R2") (pin "2") (pinfunction "2_2") (pintype "passive"))
      (node (ref "R4") (pin "2") (pinfunction "2_2") (pintype "passive"))
      (node (ref "SW1") (pin "2") (pinfunction "P_2") (pintype "passive"))
    )
    (net (code "12") (name "BAT_IN_FB") (class "Default")
      (node (ref "R1") (pin "1") (pinfunction "1_1") (pintype "passive"))
      (node (ref "ST1") (pin "52") (pinfunction "BAT_IN_FB_52") (pintype "input"))
    )
    (net (code "13") (name "BNO055_RESET") (class "Default")
      (node (ref "IC8") (pin "7") (pinfunction "IO3_7") (pintype "bidirectional"))
      (node (ref "J16") (pin "6") (pinfunction "6_6") (pintype "passive"))
    )
    (net (code "14") (name "BPS") (class "Default")
      (node (ref "J20") (pin "1") (pinfunction "1_1") (pintype "passive"))
      (node (ref "ST1") (pin "4") (pinfunction "BPS_4") (pintype "input"))
    )
    (net (code "15") (name "DEBUG_LED") (class "Default")
      (node (ref "ST1") (pin "23") (pinfunction "DEBUG_LED_23") (pintype "output"))
      (node (ref "U5") (pin "G") (pinfunction "G_G") (pintype "passive"))
    )
    (net (code "16") (name "DRV_ERW_1") (class "Default")
      (node (ref "IC9") (pin "13") (pinfunction "LED6_13") (pintype "output"))
      (node (ref "J31") (pin "2") (pinfunction "2_2") (pintype "passive"))
    )
    (net (code "17") (name "DRV_ERW_2") (class "Default")
      (node (ref "IC9") (pin "14") (pinfunction "LED7_14") (pintype "output"))
      (node (ref "J31") (pin "3") (pinfunction "3_3") (pintype "passive"))
    )
    (net (code "18") (name "DRV_KANTLED_L") (class "Default")
      (node (ref "IC9") (pin "8") (pinfunction "LED2_8") (pintype "output"))
      (node (ref "R12") (pin "2") (pinfunction "2_2") (pintype "passive"))
    )
    (net (code "19") (name "DRV_KANTLED_R") (class "Default")
      (node (ref "IC9") (pin "9") (pinfunction "LED3_9") (pintype "output"))
      (node (ref "R16") (pin "1") (pinfunction "1_1") (pintype "passive"))
    )
    (net (code "20") (name "DRV_LINE_L") (class "Default")
      (node (ref "IC9") (pin "11") (pinfunction "LED4_11") (pintype "output"))
      (node (ref "R20") (pin "2") (pinfunction "2_2") (pintype "passive"))
    )
    (net (code "21") (name "DRV_LINE_R") (class "Default")
      (node (ref "IC9") (pin "12") (pinfunction "LED5_12") (pintype "output"))
      (node (ref "R19") (pin "2") (pinfunction "2_2") (pintype "passive"))
    )
    (net (code "22") (name "DRV_RADLED_L") (class "Default")
      (node (ref "IC9") (pin "6") (pinfunction "LED0_6") (pintype "output"))
      (node (ref "R11") (pin "2") (pinfunction "2_2") (pintype "passive"))
    )
    (net (code "23") (name "DRV_RADLED_R") (class "Default")
      (node (ref "IC9") (pin "7") (pinfunction "LED1_7") (pintype "output"))
      (node (ref "R15") (pin "1") (pinfunction "1_1") (pintype "passive"))
    )
    (net (code "24") (name "EN") (class "Default")
      (node (ref "D8") (pin "1") (pinfunction "A_1") (pintype "passive"))
      (node (ref "IC12") (pin "3") (pinfunction "EN_3") (pintype "bidirectional"))
      (node (ref "R59") (pin "1") (pinfunction "1_1") (pintype "passive"))
    )
    (net (code "25") (name "ENA_AUDIO") (class "Default")
      (node (ref "IC13") (pin "12") (pinfunction "SHND_12") (pintype "input"))
      (node (ref "IC8") (pin "9") (pinfunction "IO4_9") (pintype "bidirectional"))
    )
    (net (code "26") (name "ENA_ERW_1") (class "Default")
      (node (ref "IC8") (pin "12") (pinfunction "IO7_12") (pintype "bidirectional"))
      (node (ref "J31") (pin "1") (pinfunction "1_1") (pintype "passive"))
    )
    (net (code "27") (name "ENC_L") (class "Default")
      (node (ref "R25") (pin "2") (pinfunction "2_2") (pintype "passive"))
      (node (ref "R26") (pin "1") (pinfunction "1_1") (pintype "passive"))
      (node (ref "ST2") (pin "8") (pinfunction "8_8") (pintype "passive"))
    )
    (net (code "28") (name "ENC_R") (class "Default")
      (node (ref "R31") (pin "2") (pinfunction "2_2") (pintype "passive"))
      (node (ref "R32") (pin "1") (pinfunction "1_1") (pintype "passive"))
      (node (ref "ST3") (pin "8") (pinfunction "8_8") (pintype "passive"))
    )
    (net (code "29") (name "ESP32_PROG") (class "Default")
      (node (ref "D9") (pin "2") (pinfunction "C_2") (pintype "passive"))
      (node (ref "IC8") (pin "11") (pinfunction "IO6_11") (pintype "bidirectional"))
      (node (ref "J35") (pin "2") (pinfunction "2_2") (pintype "passive"))
    )
    (net (code "30") (name "ESP32_RESET") (class "Default")
      (node (ref "D8") (pin "2") (pinfunction "C_2") (pintype "passive"))
      (node (ref "IC8") (pin "10") (pinfunction "IO5_10") (pintype "bidirectional"))
      (node (ref "J35") (pin "3") (pinfunction "3_3") (pintype "passive"))
    )
    (net (code "31") (name "FERNBED") (class "Default")
      (node (ref "J34") (pin "2") (pinfunction "2_2") (pintype "passive"))
      (node (ref "ST1") (pin "25") (pinfunction "FERNBED_25") (pintype "bidirectional"))
    )
    (net (code "32") (name "GND") (class "Default")
      (node (ref "C1") (pin "-") (pinfunction "-_-") (pintype "passive"))
      (node (ref "C10") (pin "2") (pinfunction "2_2") (pintype "passive"))
      (node (ref "C11") (pin "2") (pinfunction "2_2") (pintype "passive"))
      (node (ref "C12") (pin "2") (pinfunction "2_2") (pintype "passive"))
      (node (ref "C13") (pin "2") (pinfunction "2_2") (pintype "passive"))
      (node (ref "C14") (pin "2") (pinfunction "2_2") (pintype "passive"))
      (node (ref "C15") (pin "2") (pinfunction "2_2") (pintype "passive"))
      (node (ref "C16") (pin "-") (pinfunction "-_-") (pintype "passive"))
      (node (ref "C17") (pin "2") (pinfunction "2_2") (pintype "passive"))
      (node (ref "C18") (pin "2") (pinfunction "2_2") (pintype "passive"))
      (node (ref "C19") (pin "2") (pinfunction "2_2") (pintype "passive"))
      (node (ref "C2") (pin "2") (pinfunction "2_2") (pintype "passive"))
      (node (ref "C20") (pin "2") (pinfunction "2_2") (pintype "passive"))
      (node (ref "C21") (pin "2") (pinfunction "2_2") (pintype "passive"))
      (node (ref "C22") (pin "-") (pinfunction "-_-") (pintype "passive"))
      (node (ref "C24") (pin "2") (pinfunction "2_2") (pintype "passive"))
      (node (ref "C28") (pin "2") (pinfunction "2_2") (pintype "passive"))
      (node (ref "C29") (pin "-") (pinfunction "-_-") (pintype "passive"))
      (node (ref "C3") (pin "-") (pinfunction "-_-") (pintype "passive"))
      (node (ref "C5") (pin "-") (pinfunction "-_-") (pintype "passive"))
      (node (ref "C6") (pin "2") (pinfunction "2_2") (pintype "passive"))
      (node (ref "C7") (pin "-") (pinfunction "-_-") (pintype "passive"))
      (node (ref "C8") (pin "2") (pinfunction "2_2") (pintype "passive"))
      (node (ref "C9") (pin "-") (pinfunction "-_-") (pintype "passive"))
      (node (ref "D3") (pin "A") (pinfunction "A_A") (pintype "passive"))
      (node (ref "D4") (pin "A") (pinfunction "A_A") (pintype "passive"))
      (node (ref "IC1") (pin "3") (pinfunction "GND_3") (pintype "power_in"))
      (node (ref "IC1") (pin "5") (pinfunction "EN_5") (pintype "input"))
      (node (ref "IC1") (pin "6") (pinfunction "GND_6") (pintype "power_in"))
      (node (ref "IC10") (pin "LGND") (pinfunction "LGND_LGND") (pintype "bidirectional"))
      (node (ref "IC10") (pin "MGND") (pinfunction "MGND_MGND") (pintype "bidirectional"))
      (node (ref "IC11") (pin "3") (pinfunction "GND_3") (pintype "power_in"))
      (node (ref "IC12") (pin "1") (pinfunction "GND_1") (pintype "bidirectional"))
      (node (ref "IC12") (pin "15") (pinfunction "GND_15") (pintype "bidirectional"))
      (node (ref "IC12") (pin "24") (pinfunction "IO2_24") (pintype "bidirectional"))
      (node (ref "IC12") (pin "38") (pinfunction "GND_38") (pintype "bidirectional"))
      (node (ref "IC13") (pin "15") (pinfunction "PGND1_15") (pintype "power_in"))
      (node (ref "IC13") (pin "2") (pinfunction "PGND_2") (pintype "power_in"))
      (node (ref "IC2") (pin "3") (pinfunction "GND_3") (pintype "power_in"))
      (node (ref "IC2") (pin "5") (pinfunction "EN_5") (pintype "input"))
      (node (ref "IC2") (pin "6") (pinfunction "GND_6") (pintype "power_in"))
      (node (ref "IC3") (pin "GND") (pinfunction "GND_GND") (pintype "bidirectional"))
      (node (ref "IC4") (pin "4") (pinfunction "V-_4") (pintype "power_in"))
      (node (ref "IC7") (pin "10") (pinfunction "VSS_10") (pintype "power_in"))
      (node (ref "IC7") (pin "15") (pinfunction "OE_15") (pintype "input"))
      (node (ref "IC7") (pin "16") (pinfunction "A5_16") (pintype "input"))
      (node (ref "IC7") (pin "17") (pinfunction "A6_17") (pintype "input"))
      (node (ref "IC7") (pin "2") (pinfunction "A1_2") (pintype "input"))
      (node (ref "IC7") (pin "4") (pinfunction "A3_4") (pintype "input"))
      (node (ref "IC8") (pin "1") (pinfunction "A0_1") (pintype "input"))
      (node (ref "IC8") (pin "2") (pinfunction "A1_2") (pintype "input"))
      (node (ref "IC8") (pin "3") (pinfunction "A2_3") (pintype "input"))
      (node (ref "IC8") (pin "8") (pinfunction "VSS_8") (pintype "power_in"))
      (node (ref "IC9") (pin "10") (pinfunction "VSS_10") (pintype "power_in"))
      (node (ref "IC9") (pin "15") (pinfunction "OE_15") (pintype "input"))
      (node (ref "IC9") (pin "16") (pinfunction "A5_16") (pintype "input"))
      (node (ref "IC9") (pin "17") (pinfunction "A6_17") (pintype "input"))
      (node (ref "IC9") (pin "2") (pinfunction "A1_2") (pintype "input"))
      (node (ref "J1") (pin "2") (pinfunction "2_2") (pintype "passive"))
      (node (ref "J10") (pin "2") (pinfunction "2_2") (pintype "passive"))
      (node (ref "J13") (pin "1") (pinfunction "1_1") (pintype "passive"))
      (node (ref "J15") (pin "1") (pinfunction "1_1") (pintype "passive"))
      (node (ref "J16") (pin "3") (pinfunction "3_3") (pintype "passive"))
      (node (ref "J18") (pin "1") (pinfunction "1_1") (pintype "passive"))
      (node (ref "J19") (pin "1") (pinfunction "1_1") (pintype "passive"))
      (node (ref "J2") (pin "3") (pinfunction "3_3") (pintype "passive"))
      (node (ref "J2") (pin "4") (pinfunction "4_4") (pintype "passive"))
      (node (ref "J20") (pin "2") (pinfunction "2_2") (pintype "passive"))
      (node (ref "J25") (pin "1") (pinfunction "1_1") (pintype "passive"))
      (node (ref "J29") (pin "2") (pinfunction "2_2") (pintype "passive"))
      (node (ref "J3") (pin "1") (pinfunction "1_1") (pintype "passive"))
      (node (ref "J35") (pin "1") (pinfunction "1_1") (pintype "passive"))
      (node (ref "J5") (pin "1") (pinfunction "1_1") (pintype "passive"))
      (node (ref "J8") (pin "2") (pinfunction "2_2") (pintype "passive"))
      (node (ref "J9") (pin "2") (pinfunction "2_2") (pintype "passive"))
      (node (ref "LDR1") (pin "1") (pinfunction "P$1_1") (pintype "bidirectional"))
      (node (ref "LDR2") (pin "1") (pinfunction "P$1_1") (pintype "bidirectional"))
      (node (ref "LED1") (pin "K") (pinfunction "C_K") (pintype "passive"))
      (node (ref "LED2") (pin "K") (pinfunction "C_K") (pintype "passive"))
      (node (ref "LED3") (pin "K") (pinfunction "C_K") (pintype "passive"))
      (node (ref "R21") (pin "1") (pinfunction "A_1") (pintype "passive"))
      (node (ref "R27") (pin "1") (pinfunction "A_1") (pintype "passive"))
      (node (ref "R7") (pin "1") (pinfunction "1_1") (pintype "passive"))
      (node (ref "ST1") (pin "11") (pinfunction "GND_11") (pintype "power_in"))
      (node (ref "ST2") (pin "10") (pinfunction "10_10") (pintype "passive"))
      (node (ref "ST3") (pin "10") (pinfunction "10_10") (pintype "passive"))
      (node (ref "ST4") (pin "6") (pinfunction "6_6") (pintype "passive"))
      (node (ref "U1") (pin "3") (pinfunction "S_3") (pintype "passive"))
      (node (ref "U5") (pin "S") (pinfunction "S_S") (pintype "passive"))
    )
    (net (code "33") (name "GPIO_24") (class "Default")
      (node (ref "J32") (pin "1") (pinfunction "1_1") (pintype "passive"))
      (node (ref "ST1") (pin "2") (pinfunction "GPIO_24_2") (pintype "bidirectional"))
    )
    (net (code "34") (name "GPIO_46") (class "Default")
      (node (ref "J32") (pin "2") (pinfunction "2_2") (pintype "passive"))
      (node (ref "ST1") (pin "3") (pinfunction "GPIO_46_3") (pintype "bidirectional"))
    )
    (net (code "35") (name "IO0") (class "Default")
      (node (ref "D9") (pin "1") (pinfunction "A_1") (pintype "passive"))
      (node (ref "IC12") (pin "25") (pinfunction "IO0_25") (pintype "bidirectional"))
      (node (ref "R58") (pin "2") (pinfunction "2_2") (pintype "passive"))
    )
    (net (code "36") (name "IO4") (class "Default")
      (node (ref "IC12") (pin "26") (pinfunction "IO4_26") (pintype "bidirectional"))
    )
    (net (code "37") (name "IO5") (class "Default")
      (node (ref "IC12") (pin "29") (pinfunction "IO5_29") (pintype "bidirectional"))
    )
    (net (code "38") (name "IO6") (class "Default")
      (node (ref "IC12") (pin "20") (pinfunction "CLK_20") (pintype "bidirectional"))
    )
    (net (code "39") (name "IO7") (class "Default")
      (node (ref "IC12") (pin "21") (pinfunction "SDO_21") (pintype "bidirectional"))
    )
    (net (code "40") (name "IO8") (class "Default")
      (node (ref "IC12") (pin "22") (pinfunction "SD1_22") (pintype "bidirectional"))
    )
    (net (code "41") (name "IO9") (class "Default")
      (node (ref "IC12") (pin "17") (pinfunction "SD2_17") (pintype "bidirectional"))
    )
    (net (code "42") (name "IO10") (class "Default")
      (node (ref "IC12") (pin "18") (pinfunction "SD3_18") (pintype "bidirectional"))
    )
    (net (code "43") (name "IO11") (class "Default")
      (node (ref "IC12") (pin "19") (pinfunction "CMD_19") (pintype "bidirectional"))
    )
    (net (code "44") (name "IO13") (class "Default")
      (node (ref "IC12") (pin "16") (pinfunction "IO13_16") (pintype "bidirectional"))
    )
    (net (code "45") (name "IO15") (class "Default")
      (node (ref "IC12") (pin "23") (pinfunction "IO15_23") (pintype "bidirectional"))
    )
    (net (code "46") (name "IO18") (class "Default")
      (node (ref "IC12") (pin "30") (pinfunction "IO18_30") (pintype "bidirectional"))
    )
    (net (code "47") (name "IO19") (class "Default")
      (node (ref "IC12") (pin "31") (pinfunction "IO19_31") (pintype "bidirectional"))
    )
    (net (code "48") (name "IO21") (class "Default")
      (node (ref "IC12") (pin "33") (pinfunction "IO21_33") (pintype "bidirectional"))
    )
    (net (code "49") (name "IO34") (class "Default")
      (node (ref "IC12") (pin "6") (pinfunction "IO34_6") (pintype "bidirectional"))
      (node (ref "J7") (pin "2") (pinfunction "2_2") (pintype "passive"))
    )
    (net (code "50") (name "IO35") (class "Default")
      (node (ref "IC12") (pin "7") (pinfunction "IO35_7") (pintype "bidirectional"))
      (node (ref "J7") (pin "1") (pinfunction "1_1") (pintype "passive"))
    )
    (net (code "51") (name "IO36") (class "Default")
      (node (ref "IC12") (pin "4") (pinfunction "SENSOR_VP_4") (pintype "bidirectional"))
      (node (ref "J7") (pin "3") (pinfunction "3_3") (pintype "passive"))
    )
    (net (code "52") (name "IO39") (class "Default")
      (node (ref "IC12") (pin "5") (pinfunction "SENSOR_VN_5") (pintype "bidirectional"))
    )
    (net (code "53") (name "KANTE_L") (class "Default")
      (node (ref "R13") (pin "1") (pinfunction "1_1") (pintype "passive"))
      (node (ref "ST1") (pin "54") (pinfunction "KANTE_L_54") (pintype "input"))
      (node (ref "ST2") (pin "9") (pinfunction "9_9") (pintype "passive"))
    )
    (net (code "54") (name "KANTE_R") (class "Default")
      (node (ref "R14") (pin "2") (pinfunction "2_2") (pintype "passive"))
      (node (ref "ST1") (pin "55") (pinfunction "KANTE_R_55") (pintype "input"))
      (node (ref "ST3") (pin "9") (pinfunction "9_9") (pintype "passive"))
    )
    (net (code "55") (name "KL02_DC") (class "Default")
      (node (ref "IC12") (pin "14") (pinfunction "IO12_14") (pintype "bidirectional"))
      (node (ref "J30") (pin "1") (pinfunction "1_1") (pintype "passive"))
    )
    (net (code "56") (name "KL02_DD") (class "Default")
      (node (ref "IC12") (pin "13") (pinfunction "IO14_13") (pintype "bidirectional"))
      (node (ref "J30") (pin "2") (pinfunction "2_2") (pintype "passive"))
    )
    (net (code "57") (name "LDR_L") (class "Default")
      (node (ref "LDR1") (pin "2") (pinfunction "P$2_2") (pintype "bidirectional"))
      (node (ref "R34") (pin "1") (pinfunction "1_1") (pintype "passive"))
      (node (ref "ST1") (pin "53") (pinfunction "LDR_L_53") (pintype "input"))
    )
    (net (code "58") (name "LDR_R") (class "Default")
      (node (ref "LDR2") (pin "2") (pinfunction "P$2_2") (pintype "bidirectional"))
      (node (ref "R35") (pin "1") (pinfunction "1_1") (pintype "passive"))
      (node (ref "ST1") (pin "56") (pinfunction "LDR_R_56") (pintype "input"))
    )
    (net (code "59") (name "LINE_IN_L") (class "Default")
      (node (ref "J28") (pin "2") (pinfunction "2_2") (pintype "passive"))
      (node (ref "R60") (pin "1") (pinfunction "A_1") (pintype "passive"))
    )
    (net (code "60") (name "LINE_IN_R") (class "Default")
      (node (ref "C27") (pin "2") (pinfunction "2_2") (pintype "passive"))
      (node (ref "J28") (pin "3") (pinfunction "3_3") (pintype "passive"))
    )
    (net (code "61") (name "LINIE_L") (class "Default")
      (node (ref "R18") (pin "1") (pinfunction "1_1") (pintype "passive"))
      (node (ref "ST1") (pin "51") (pinfunction "LINIE_L_51") (pintype "input"))
      (node (ref "ST4") (pin "4") (pinfunction "4_4") (pintype "passive"))
    )
    (net (code "62") (name "LINIE_R") (class "Default")
      (node (ref "R17") (pin "1") (pinfunction "1_1") (pintype "passive"))
      (node (ref "ST1") (pin "50") (pinfunction "LINIE_R_50") (pintype "input"))
      (node (ref "ST4") (pin "5") (pinfunction "5_5") (pintype "passive"))
    )
    (net (code "63") (name "MOT_L_2") (class "Default")
      (node (ref "IC10") (pin "AOUT2") (pinfunction "AOUT2_AOUT2") (pintype "bidirectional"))
      (node (ref "ST6") (pin "2") (pinfunction "2_2") (pintype "passive"))
    )
    (net (code "64") (name "MOT_L_DIR") (class "Default")
      (node (ref "IC10") (pin "APHASE") (pinfunction "APHASE_APHASE") (pintype "bidirectional"))
      (node (ref "ST1") (pin "19") (pinfunction "MOT_L_DIR_19") (pintype "output"))
    )
    (net (code "65") (name "MOT_L_PWM") (class "Default")
      (node (ref "IC10") (pin "AENBL") (pinfunction "AENBL_AENBL") (pintype "bidirectional"))
      (node (ref "ST1") (pin "20") (pinfunction "MOT_L_PWM_20") (pintype "output"))
    )
    (net (code "66") (name "MOT_R_2") (class "Default")
      (node (ref "IC10") (pin "BOUT2") (pinfunction "BOUT2_BOUT2") (pintype "bidirectional"))
      (node (ref "ST5") (pin "2") (pinfunction "2_2") (pintype "passive"))
    )
    (net (code "67") (name "MOT_R_DIR") (class "Default")
      (node (ref "IC10") (pin "BPHASE") (pinfunction "BPHASE_BPHASE") (pintype "bidirectional"))
      (node (ref "ST1") (pin "21") (pinfunction "MOT_R_DIR_21") (pintype "output"))
    )
    (net (code "68") (name "MOT_R_PWM") (class "Default")
      (node (ref "IC10") (pin "BENBL") (pinfunction "BENBL_BENBL") (pintype "bidirectional"))
      (node (ref "ST1") (pin "22") (pinfunction "MOT_R_PWM_22") (pintype "output"))
    )
    (net (code "69") (name "Net-(C23-Pad1)") (class "Default")
      (node (ref "C23") (pin "1") (pinfunction "1_1") (pintype "passive"))
      (node (ref "R61") (pin "2") (pinfunction "2_2") (pintype "passive"))
    )
    (net (code "70") (name "Net-(C27-Pad1)") (class "Default")
      (node (ref "C27") (pin "1") (pinfunction "1_1") (pintype "passive"))
      (node (ref "R62") (pin "2") (pinfunction "2_2") (pintype "passive"))
    )
    (net (code "71") (name "Net-(D1-PadA)") (class "Default")
      (node (ref "D1") (pin "A") (pinfunction "A_A") (pintype "passive"))
      (node (ref "D2") (pin "C") (pinfunction "C_C") (pintype "passive"))
      (node (ref "R1") (pin "2") (pinfunction "2_2") (pintype "passive"))
      (node (ref "R2") (pin "1") (pinfunction "1_1") (pintype "passive"))
      (node (ref "R3") (pin "2") (pinfunction "2_2") (pintype "passive"))
    )
    (net (code "72") (name "Net-(D5-A)") (class "Default")
      (node (ref "D5") (pin "1") (pinfunction "A_1") (pintype "passive"))
      (node (ref "ST2") (pin "4") (pinfunction "4_4") (pintype "passive"))
    )
    (net (code "73") (name "Net-(D6-A)") (class "Default")
      (node (ref "D6") (pin "1") (pinfunction "A_1") (pintype "passive"))
      (node (ref "ST2") (pin "5") (pinfunction "5_5") (pintype "passive"))
    )
    (net (code "74") (name "Net-(D7-A)") (class "Default")
      (node (ref "D7") (pin "1") (pinfunction "A_1") (pintype "passive"))
      (node (ref "ST3") (pin "4") (pinfunction "4_4") (pintype "passive"))
    )
    (net (code "75") (name "Net-(IC1-FB)") (class "Default")
      (node (ref "C4") (pin "2") (pinfunction "2_2") (pintype "passive"))
      (node (ref "IC1") (pin "4") (pinfunction "FB_4") (pintype "input"))
      (node (ref "R6") (pin "1") (pinfunction "1_1") (pintype "passive"))
      (node (ref "R7") (pin "2") (pinfunction "2_2") (pintype "passive"))
    )
    (net (code "76") (name "Net-(IC1-OUT)") (class "Default")
      (node (ref "D3") (pin "C") (pinfunction "C_C") (pintype "passive"))
      (node (ref "IC1") (pin "2") (pinfunction "OUT_2") (pintype "output"))
      (node (ref "L1") (pin "1") (pinfunction "1_1") (pintype "passive"))
    )
    (net (code "77") (name "Net-(IC2-OUT)") (class "Default")
      (node (ref "D4") (pin "C") (pinfunction "C_C") (pintype "passive"))
      (node (ref "IC2") (pin "2") (pinfunction "OUT_2") (pintype "output"))
      (node (ref "L2") (pin "1") (pinfunction "1_1") (pintype "passive"))
    )
    (net (code "78") (name "Net-(IC4A-+IN)") (class "Default")
      (node (ref "IC4") (pin "3") (pinfunction "+IN_3") (pintype "input"))
      (node (ref "R22") (pin "2") (pinfunction "2_2") (pintype "passive"))
      (node (ref "R23") (pin "1") (pinfunction "1_1") (pintype "passive"))
    )
    (net (code "79") (name "Net-(IC4A--IN)") (class "Default")
      (node (ref "IC4") (pin "2") (pinfunction "-IN_2") (pintype "input"))
      (node (ref "R25") (pin "1") (pinfunction "1_1") (pintype "passive"))
    )
    (net (code "80") (name "Net-(IC4B-+IN)") (class "Default")
      (node (ref "IC4") (pin "5") (pinfunction "+IN_5") (pintype "input"))
      (node (ref "R28") (pin "2") (pinfunction "2_2") (pintype "passive"))
      (node (ref "R29") (pin "1") (pinfunction "1_1") (pintype "passive"))
    )
    (net (code "81") (name "Net-(IC4B--IN)") (class "Default")
      (node (ref "IC4") (pin "6") (pinfunction "-IN_6") (pintype "input"))
      (node (ref "R31") (pin "1") (pinfunction "1_1") (pintype "passive"))
    )
    (net (code "82") (name "Net-(IC7-LED0)") (class "Default")
      (node (ref "IC7") (pin "6") (pinfunction "LED0_6") (pintype "output"))
      (node (ref "LED12") (pin "K") (pinfunction "C_K") (pintype "passive"))
    )
    (net (code "83") (name "Net-(IC7-LED1)") (class "Default")
      (node (ref "IC7") (pin "7") (pinfunction "LED1_7") (pintype "output"))
      (node (ref "LED11") (pin "K") (pinfunction "C_K") (pintype "passive"))
    )
    (net (code "84") (name "Net-(IC7-LED2)") (class "Default")
      (node (ref "IC7") (pin "8") (pinfunction "LED2_8") (pintype "output"))
      (node (ref "LED10") (pin "K") (pinfunction "C_K") (pintype "passive"))
    )
    (net (code "85") (name "Net-(IC7-LED3)") (class "Default")
      (node (ref "IC7") (pin "9") (pinfunction "LED3_9") (pintype "output"))
      (node (ref "LED9") (pin "K") (pinfunction "C_K") (pintype "passive"))
    )
    (net (code "86") (name "Net-(IC7-LED4)") (class "Default")
      (node (ref "IC7") (pin "11") (pinfunction "LED4_11") (pintype "output"))
      (node (ref "LED8") (pin "K") (pinfunction "C_K") (pintype "passive"))
    )
    (net (code "87") (name "Net-(IC7-LED5)") (class "Default")
      (node (ref "IC7") (pin "12") (pinfunction "LED5_12") (pintype "output"))
      (node (ref "LED7") (pin "K") (pinfunction "C_K") (pintype "passive"))
    )
    (net (code "88") (name "Net-(IC7-LED6)") (class "Default")
      (node (ref "IC7") (pin "13") (pinfunction "LED6_13") (pintype "output"))
      (node (ref "LED6") (pin "K") (pinfunction "C_K") (pintype "passive"))
    )
    (net (code "89") (name "Net-(IC7-LED7)") (class "Default")
      (node (ref "IC7") (pin "14") (pinfunction "LED7_14") (pintype "output"))
      (node (ref "LED5") (pin "K") (pinfunction "C_K") (pintype "passive"))
    )
    (net (code "90") (name "Net-(IC10-PadAOUT1)") (class "Default")
      (node (ref "IC10") (pin "AOUT1") (pinfunction "AOUT1_AOUT1") (pintype "bidirectional"))
      (node (ref "ST6") (pin "1") (pinfunction "1_1") (pintype "passive"))
    )
    (net (code "91") (name "Net-(IC10-PadBOUT1)") (class "Default")
      (node (ref "IC10") (pin "BOUT1") (pinfunction "BOUT1_BOUT1") (pintype "bidirectional"))
      (node (ref "ST5") (pin "1") (pinfunction "1_1") (pintype "passive"))
    )
    (net (code "92") (name "Net-(IC10-PadMODE)") (class "Default")
      (node (ref "IC10") (pin "MODE") (pinfunction "MODE_MODE") (pintype "bidirectional"))
      (node (ref "J6") (pin "2") (pinfunction "2_2") (pintype "passive"))
    )
    (net (code "93") (name "Net-(IC11-OUT)") (class "Default")
      (node (ref "IC11") (pin "1") (pinfunction "OUT_1") (pintype "output"))
      (node (ref "J34") (pin "1") (pinfunction "1_1") (pintype "passive"))
    )
    (net (code "94") (name "Net-(IC13-+OUT_L)") (class "Default")
      (node (ref "IC13") (pin "1") (pinfunction "+OUT_L_1") (pintype "output"))
      (node (ref "J26") (pin "2") (pinfunction "2_2") (pintype "passive"))
    )
    (net (code "95") (name "Net-(IC13-+OUT_R)") (class "Default")
      (node (ref "IC13") (pin "16") (pinfunction "+OUT_R_16") (pintype "output"))
      (node (ref "J27") (pin "2") (pinfunction "2_2") (pintype "passive"))
    )
    (net (code "96") (name "Net-(IC13--OUT_L)") (class "Default")
      (node (ref "IC13") (pin "3") (pinfunction "-OUT_L_3") (pintype "output"))
      (node (ref "J26") (pin "1") (pinfunction "1_1") (pintype "passive"))
    )
    (net (code "97") (name "Net-(IC13--OUT_R)") (class "Default")
      (node (ref "IC13") (pin "14") (pinfunction "-OUT_R_14") (pintype "output"))
      (node (ref "J27") (pin "1") (pinfunction "1_1") (pintype "passive"))
    )
    (net (code "98") (name "Net-(IC13-INL)") (class "Default")
      (node (ref "IC13") (pin "7") (pinfunction "INL_7") (pintype "input"))
      (node (ref "R61") (pin "1") (pinfunction "1_1") (pintype "passive"))
    )
    (net (code "99") (name "Net-(IC13-INR)") (class "Default")
      (node (ref "IC13") (pin "10") (pinfunction "INR_10") (pintype "input"))
      (node (ref "R62") (pin "1") (pinfunction "1_1") (pintype "passive"))
    )
    (net (code "100") (name "Net-(IC13-VREF)") (class "Default")
      (node (ref "C26") (pin "1") (pinfunction "1_1") (pintype "passive"))
      (node (ref "IC13") (pin "8") (pinfunction "VREF_8") (pintype "passive"))
    )
    (net (code "101") (name "Net-(LED1-PadA)") (class "Default")
      (node (ref "LED1") (pin "A") (pinfunction "A_A") (pintype "passive"))
      (node (ref "R8") (pin "2") (pinfunction "2_2") (pintype "passive"))
    )
    (net (code "102") (name "Net-(LED2-PadA)") (class "Default")
      (node (ref "LED2") (pin "A") (pinfunction "A_A") (pintype "passive"))
      (node (ref "R9") (pin "1") (pinfunction "1_1") (pintype "passive"))
    )
    (net (code "103") (name "Net-(LED3-PadA)") (class "Default")
      (node (ref "LED3") (pin "A") (pinfunction "A_A") (pintype "passive"))
      (node (ref "R10") (pin "1") (pinfunction "1_1") (pintype "passive"))
    )
    (net (code "104") (name "Net-(LED4-C)") (class "Default")
      (node (ref "LED4") (pin "K") (pinfunction "C_K") (pintype "passive"))
      (node (ref "U5") (pin "D") (pinfunction "D_D") (pintype "passive"))
    )
    (net (code "105") (name "Net-(LED4-PadA)") (class "Default")
      (node (ref "LED4") (pin "A") (pinfunction "A_A") (pintype "passive"))
      (node (ref "R33") (pin "1") (pinfunction "1_1") (pintype "passive"))
    )
    (net (code "106") (name "Net-(LED5-PadA)") (class "Default")
      (node (ref "LED5") (pin "A") (pinfunction "A_A") (pintype "passive"))
      (node (ref "R44") (pin "2") (pinfunction "2_2") (pintype "passive"))
    )
    (net (code "107") (name "Net-(LED6-PadA)") (class "Default")
      (node (ref "LED6") (pin "A") (pinfunction "A_A") (pintype "passive"))
      (node (ref "R45") (pin "2") (pinfunction "2_2") (pintype "passive"))
    )
    (net (code "108") (name "Net-(LED7-PadA)") (class "Default")
      (node (ref "LED7") (pin "A") (pinfunction "A_A") (pintype "passive"))
      (node (ref "R46") (pin "2") (pinfunction "2_2") (pintype "passive"))
    )
    (net (code "109") (name "Net-(LED8-PadA)") (class "Default")
      (node (ref "LED8") (pin "A") (pinfunction "A_A") (pintype "passive"))
      (node (ref "R47") (pin "2") (pinfunction "2_2") (pintype "passive"))
    )
    (net (code "110") (name "Net-(LED9-PadA)") (class "Default")
      (node (ref "LED9") (pin "A") (pinfunction "A_A") (pintype "passive"))
      (node (ref "R48") (pin "2") (pinfunction "2_2") (pintype "passive"))
    )
    (net (code "111") (name "Net-(LED10-PadA)") (class "Default")
      (node (ref "LED10") (pin "A") (pinfunction "A_A") (pintype "passive"))
      (node (ref "R49") (pin "2") (pinfunction "2_2") (pintype "passive"))
    )
    (net (code "112") (name "Net-(LED11-PadA)") (class "Default")
      (node (ref "LED11") (pin "A") (pinfunction "A_A") (pintype "passive"))
      (node (ref "R50") (pin "2") (pinfunction "2_2") (pintype "passive"))
    )
    (net (code "113") (name "Net-(LED12-PadA)") (class "Default")
      (node (ref "LED12") (pin "A") (pinfunction "A_A") (pintype "passive"))
      (node (ref "R51") (pin "2") (pinfunction "2_2") (pintype "passive"))
    )
    (net (code "114") (name "Net-(R11-Pad1)") (class "Default")
      (node (ref "R11") (pin "1") (pinfunction "1_1") (pintype "passive"))
      (node (ref "ST2") (pin "6") (pinfunction "6_6") (pintype "passive"))
    )
    (net (code "115") (name "Net-(R12-Pad1)") (class "Default")
      (node (ref "R12") (pin "1") (pinfunction "1_1") (pintype "passive"))
      (node (ref "ST2") (pin "7") (pinfunction "7_7") (pintype "passive"))
    )
    (net (code "116") (name "Net-(R15-Pad2)") (class "Default")
      (node (ref "R15") (pin "2") (pinfunction "2_2") (pintype "passive"))
      (node (ref "ST3") (pin "6") (pinfunction "6_6") (pintype "passive"))
    )
    (net (code "117") (name "Net-(R16-Pad2)") (class "Default")
      (node (ref "R16") (pin "2") (pinfunction "2_2") (pintype "passive"))
      (node (ref "ST3") (pin "7") (pinfunction "7_7") (pintype "passive"))
    )
    (net (code "118") (name "Net-(R19-Pad1)") (class "Default")
      (node (ref "R19") (pin "1") (pinfunction "1_1") (pintype "passive"))
      (node (ref "ST4") (pin "3") (pinfunction "3_3") (pintype "passive"))
    )
    (net (code "119") (name "Net-(R20-Pad1)") (class "Default")
      (node (ref "R20") (pin "1") (pinfunction "1_1") (pintype "passive"))
      (node (ref "ST4") (pin "2") (pinfunction "2_2") (pintype "passive"))
    )
    (net (code "120") (name "Net-(R21-S)") (class "Default")
      (node (ref "C10") (pin "1") (pinfunction "1_1") (pintype "passive"))
      (node (ref "R21") (pin "2") (pinfunction "S_2") (pintype "passive"))
      (node (ref "R22") (pin "1") (pinfunction "1_1") (pintype "passive"))
    )
    (net (code "121") (name "Net-(R27-S)") (class "Default")
      (node (ref "C13") (pin "1") (pinfunction "1_1") (pintype "passive"))
      (node (ref "R27") (pin "2") (pinfunction "S_2") (pintype "passive"))
      (node (ref "R28") (pin "1") (pinfunction "1_1") (pintype "passive"))
    )
    (net (code "122") (name "Net-(R60-S)") (class "Default")
      (node (ref "C23") (pin "2") (pinfunction "2_2") (pintype "passive"))
      (node (ref "R60") (pin "2") (pinfunction "S_2") (pintype "passive"))
    )
    (net (code "123") (name "Net-(U1-G)") (class "Default")
      (node (ref "R4") (pin "1") (pinfunction "1_1") (pintype "passive"))
      (node (ref "U1") (pin "1") (pinfunction "G_1") (pintype "passive"))
    )
    (net (code "124") (name "PWM_ERW_1") (class "Default")
      (node (ref "ST1") (pin "39") (pinfunction "PWM_ERW_1_39") (pintype "bidirectional"))
    )
    (net (code "125") (name "PWM_ERW_2") (class "Default")
      (node (ref "ST1") (pin "40") (pinfunction "PWM_ERW_2_40") (pintype "bidirectional"))
    )
    (net (code "126") (name "PWM_ERW_3") (class "Default")
      (node (ref "J8") (pin "9") (pinfunction "9_9") (pintype "passive"))
      (node (ref "ST1") (pin "42") (pinfunction "PWM_ERW_3_42") (pintype "bidirectional"))
    )
    (net (code "127") (name "PWM_ERW_4") (class "Default")
      (node (ref "ST1") (pin "41") (pinfunction "PWM_ERW_4_41") (pintype "bidirectional"))
    )
    (net (code "128") (name "PWM_ERW_5") (class "Default")
      (node (ref "ST1") (pin "43") (pinfunction "PWM_ERW_5_43") (pintype "bidirectional"))
    )
    (net (code "129") (name "PWM_ERW_6") (class "Default")
      (node (ref "ST1") (pin "44") (pinfunction "PWM_ERW_6_44") (pintype "bidirectional"))
    )
    (net (code "130") (name "RAD_L") (class "Default")
      (node (ref "C11") (pin "1") (pinfunction "1_1") (pintype "passive"))
      (node (ref "C12") (pin "1") (pinfunction "1_1") (pintype "passive"))
      (node (ref "IC4") (pin "1") (pinfunction "OUT_1") (pintype "output"))
      (node (ref "R23") (pin "2") (pinfunction "2_2") (pintype "passive"))
      (node (ref "R24") (pin "1") (pinfunction "1_1") (pintype "passive"))
      (node (ref "ST1") (pin "12") (pinfunction "RAD_L_12") (pintype "input"))
    )
    (net (code "131") (name "RAD_R") (class "Default")
      (node (ref "C14") (pin "1") (pinfunction "1_1") (pintype "passive"))
      (node (ref "C15") (pin "1") (pinfunction "1_1") (pintype "passive"))
      (node (ref "IC4") (pin "7") (pinfunction "OUT_7") (pintype "output"))
      (node (ref "R29") (pin "2") (pinfunction "2_2") (pintype "passive"))
      (node (ref "R30") (pin "1") (pinfunction "1_1") (pintype "passive"))
      (node (ref "ST1") (pin "13") (pinfunction "RAD_R_13") (pintype "input"))
    )
    (net (code "132") (name "RESET") (class "Default")
      (node (ref "IC12") (pin "36") (pinfunction "IO22_36") (pintype "bidirectional"))
      (node (ref "J29") (pin "1") (pinfunction "1_1") (pintype "passive"))
      (node (ref "ST1") (pin "24") (pinfunction "RESET_24") (pintype "input"))
    )
    (net (code "133") (name "RX1") (class "Default")
      (node (ref "J37") (pin "2") (pinfunction "2_2") (pintype "passive"))
      (node (ref "ST1") (pin "26") (pinfunction "RX1_26") (pintype "input"))
    )
    (net (code "134") (name "RX2") (class "Default")
      (node (ref "ST1") (pin "28") (pinfunction "RX2_28") (pintype "input"))
    )
    (net (code "135") (name "RX5") (class "Default")
      (node (ref "IC12") (pin "28") (pinfunction "IO17_28") (pintype "bidirectional"))
      (node (ref "J18") (pin "4") (pinfunction "4_4") (pintype "passive"))
      (node (ref "ST1") (pin "30") (pinfunction "RX5_30") (pintype "input"))
    )
    (net (code "136") (name "RX6") (class "Default")
      (node (ref "J19") (pin "4") (pinfunction "4_4") (pintype "passive"))
      (node (ref "ST1") (pin "32") (pinfunction "RX6_32") (pintype "input"))
    )
    (net (code "137") (name "RXD0") (class "Default")
      (node (ref "IC12") (pin "34") (pinfunction "RXD0_34") (pintype "bidirectional"))
      (node (ref "J25") (pin "3") (pinfunction "3_3") (pintype "passive"))
    )
    (net (code "138") (name "SCHRANKE_SHDN") (class "Default")
      (node (ref "D6") (pin "2") (pinfunction "C_2") (pintype "passive"))
      (node (ref "IC8") (pin "6") (pinfunction "IO2_6") (pintype "bidirectional"))
    )
    (net (code "139") (name "SCL0") (class "Default")
      (node (ref "J13") (pin "4") (pinfunction "4_4") (pintype "passive"))
      (node (ref "R37") (pin "1") (pinfunction "1_1") (pintype "passive"))
      (node (ref "ST1") (pin "60") (pinfunction "SCL0_60") (pintype "output"))
      (node (ref "U6") (pin "S") (pinfunction "S_S") (pintype "passive"))
    )
    (net (code "140") (name "SCL0_5V") (class "Default")
      (node (ref "IC7") (pin "18") (pinfunction "SCL_18") (pintype "input"))
      (node (ref "IC8") (pin "14") (pinfunction "SCL_14") (pintype "input"))
      (node (ref "IC9") (pin "18") (pinfunction "SCL_18") (pintype "input"))
      (node (ref "J16") (pin "5") (pinfunction "5_5") (pintype "passive"))
      (node (ref "J3") (pin "4") (pinfunction "4_4") (pintype "passive"))
      (node (ref "R39") (pin "1") (pinfunction "1_1") (pintype "passive"))
      (node (ref "ST1") (pin "45") (pinfunction "SCL0_5V_45") (pintype "output"))
      (node (ref "ST2") (pin "3") (pinfunction "3_3") (pintype "passive"))
      (node (ref "ST3") (pin "3") (pinfunction "3_3") (pintype "passive"))
      (node (ref "U6") (pin "D") (pinfunction "D_D") (pintype "passive"))
    )
    (net (code "141") (name "SCL1") (class "Default")
      (node (ref "ST1") (pin "61") (pinfunction "SCL1_61") (pintype "output"))
    )
    (net (code "142") (name "SCL3") (class "Default")
      (node (ref "IC12") (pin "11") (pinfunction "IO26_11") (pintype "bidirectional"))
      (node (ref "J15") (pin "3") (pinfunction "3_3") (pintype "passive"))
      (node (ref "R41") (pin "1") (pinfunction "1_1") (pintype "passive"))
      (node (ref "ST1") (pin "64") (pinfunction "SCL3_64") (pintype "output"))
    )
    (net (code "143") (name "SDA0") (class "Default")
      (node (ref "J13") (pin "3") (pinfunction "3_3") (pintype "passive"))
      (node (ref "R36") (pin "1") (pinfunction "1_1") (pintype "passive"))
      (node (ref "ST1") (pin "59") (pinfunction "SDA0_59") (pintype "bidirectional"))
      (node (ref "U7") (pin "S") (pinfunction "S_S") (pintype "passive"))
    )
    (net (code "144") (name "SDA0_5V") (class "Default")
      (node (ref "IC7") (pin "19") (pinfunction "SDA_19") (pintype "bidirectional"))
      (node (ref "IC8") (pin "15") (pinfunction "SDA_15") (pintype "bidirectional"))
      (node (ref "IC9") (pin "19") (pinfunction "SDA_19") (pintype "bidirectional"))
      (node (ref "J16") (pin "4") (pinfunction "4_4") (pintype "passive"))
      (node (ref "J3") (pin "3") (pinfunction "3_3") (pintype "passive"))
      (node (ref "R38") (pin "1") (pinfunction "1_1") (pintype "passive"))
      (node (ref "ST1") (pin "46") (pinfunction "SDA0_5V_46") (pintype "bidirectional"))
      (node (ref "ST2") (pin "2") (pinfunction "2_2") (pintype "passive"))
      (node (ref "ST3") (pin "2") (pinfunction "2_2") (pintype "passive"))
      (node (ref "U7") (pin "D") (pinfunction "D_D") (pintype "passive"))
    )
    (net (code "145") (name "SDA1") (class "Default")
      (node (ref "ST1") (pin "62") (pinfunction "SDA1_62") (pintype "bidirectional"))
    )
    (net (code "146") (name "SDA3") (class "Default")
      (node (ref "IC12") (pin "10") (pinfunction "IO25_10") (pintype "bidirectional"))
      (node (ref "J15") (pin "4") (pinfunction "4_4") (pintype "passive"))
      (node (ref "R40") (pin "1") (pinfunction "1_1") (pintype "passive"))
      (node (ref "ST1") (pin "63") (pinfunction "SDA3_63") (pintype "bidirectional"))
    )
    (net (code "147") (name "SERVO1_FB") (class "Default")
      (node (ref "J5") (pin "4") (pinfunction "4_4") (pintype "passive"))
      (node (ref "ST1") (pin "57") (pinfunction "SERVO1_FB_57") (pintype "input"))
    )
    (net (code "148") (name "SERVO1_PWM") (class "Default")
      (node (ref "J5") (pin "3") (pinfunction "3_3") (pintype "passive"))
      (node (ref "R55") (pin "1") (pinfunction "1_1") (pintype "passive"))
      (node (ref "ST1") (pin "14") (pinfunction "SERVO1_PWM_14") (pintype "output"))
    )
    (net (code "149") (name "SERVO2_FB") (class "Default")
      (node (ref "ST1") (pin "58") (pinfunction "SERVO2_FB_58") (pintype "input"))
    )
    (net (code "150") (name "SERVO2_PWM") (class "Default")
      (node (ref "ST1") (pin "15") (pinfunction "SERVO2_PWM_15") (pintype "output"))
    )
    (net (code "151") (name "SERVO3_PWM") (class "Default")
      (node (ref "ST1") (pin "16") (pinfunction "SERVO3_PWM_16") (pintype "bidirectional"))
    )
    (net (code "152") (name "SERVO4_PWM") (class "Default")
      (node (ref "J10") (pin "6") (pinfunction "6_6") (pintype "passive"))
      (node (ref "J9") (pin "6") (pinfunction "6_6") (pintype "passive"))
      (node (ref "ST1") (pin "17") (pinfunction "SERVO4_PWM_17") (pintype "bidirectional"))
    )
    (net (code "153") (name "SERVO5_PWM") (class "Default")
      (node (ref "J9") (pin "7") (pinfunction "7_7") (pintype "passive"))
      (node (ref "ST1") (pin "18") (pinfunction "SERVO5_PWM_18") (pintype "bidirectional"))
    )
    (net (code "154") (name "SPI0_CS0") (class "Default")
      (node (ref "J8") (pin "6") (pinfunction "6_6") (pintype "passive"))
      (node (ref "ST1") (pin "8") (pinfunction "SPI0_CS0_8") (pintype "bidirectional"))
    )
    (net (code "155") (name "SPI0_CS4") (class "Default")
      (node (ref "J8") (pin "7") (pinfunction "7_7") (pintype "passive"))
      (node (ref "ST1") (pin "9") (pinfunction "SPI0_CS4_9") (pintype "bidirectional"))
    )
    (net (code "156") (name "SPI0_CS5") (class "Default")
      (node (ref "J8") (pin "8") (pinfunction "8_8") (pintype "passive"))
      (node (ref "ST1") (pin "10") (pinfunction "SPI0_CS5_10") (pintype "bidirectional"))
    )
    (net (code "157") (name "SPI0_MISO") (class "Default")
      (node (ref "J10") (pin "4") (pinfunction "4_4") (pintype "passive"))
      (node (ref "J8") (pin "4") (pinfunction "4_4") (pintype "passive"))
      (node (ref "J9") (pin "4") (pinfunction "4_4") (pintype "passive"))
      (node (ref "ST1") (pin "6") (pinfunction "SPI0_MISO_6") (pintype "bidirectional"))
    )
    (net (code "158") (name "SPI0_MOSI") (class "Default")
      (node (ref "J10") (pin "3") (pinfunction "3_3") (pintype "passive"))
      (node (ref "J8") (pin "3") (pinfunction "3_3") (pintype "passive"))
      (node (ref "J9") (pin "3") (pinfunction "3_3") (pintype "passive"))
      (node (ref "ST1") (pin "5") (pinfunction "SPI0_MOSI_5") (pintype "bidirectional"))
    )
    (net (code "159") (name "SPI0_SCK") (class "Default")
      (node (ref "J10") (pin "5") (pinfunction "5_5") (pintype "passive"))
      (node (ref "J8") (pin "5") (pinfunction "5_5") (pintype "passive"))
      (node (ref "J9") (pin "5") (pinfunction "5_5") (pintype "passive"))
      (node (ref "ST1") (pin "7") (pinfunction "SPI0_SCK_7") (pintype "bidirectional"))
    )
    (net (code "160") (name "SPI1_CS0") (class "Default")
      (node (ref "J36") (pin "4") (pinfunction "4_4") (pintype "passive"))
      (node (ref "ST1") (pin "68") (pinfunction "SPI1_CS0_68") (pintype "bidirectional"))
    )
    (net (code "161") (name "SPI1_MISO") (class "Default")
      (node (ref "J36") (pin "2") (pinfunction "2_2") (pintype "passive"))
      (node (ref "ST1") (pin "66") (pinfunction "SPI1_MISO_66") (pintype "bidirectional"))
    )
    (net (code "162") (name "SPI1_MOSI") (class "Default")
      (node (ref "J36") (pin "1") (pinfunction "1_1") (pintype "passive"))
      (node (ref "ST1") (pin "65") (pinfunction "SPI1_MOSI_65") (pintype "bidirectional"))
    )
    (net (code "163") (name "SPI1_SCK") (class "Default")
      (node (ref "J36") (pin "3") (pinfunction "3_3") (pintype "passive"))
      (node (ref "ST1") (pin "67") (pinfunction "SPI1_SCK_67") (pintype "bidirectional"))
    )
    (net (code "164") (name "SWCLK") (class "Default")
      (node (ref "IC12") (pin "9") (pinfunction "IO33_9") (pintype "bidirectional"))
      (node (ref "J29") (pin "4") (pinfunction "4_4") (pintype "passive"))
    )
    (net (code "165") (name "SWDIO") (class "Default")
      (node (ref "IC12") (pin "8") (pinfunction "IO32_8") (pintype "bidirectional"))
      (node (ref "J29") (pin "5") (pinfunction "5_5") (pintype "passive"))
    )
    (net (code "166") (name "SWD_EN") (class "Default")
      (node (ref "IC12") (pin "12") (pinfunction "IO27_12") (pintype "bidirectional"))
      (node (ref "J29") (pin "3") (pinfunction "3_3") (pintype "passive"))
    )
    (net (code "167") (name "TX1") (class "Default")
      (node (ref "J37") (pin "1") (pinfunction "1_1") (pintype "passive"))
      (node (ref "ST1") (pin "27") (pinfunction "TX1_27") (pintype "output"))
    )
    (net (code "168") (name "TX2") (class "Default")
      (node (ref "ST1") (pin "29") (pinfunction "TX2_29") (pintype "input"))
    )
    (net (code "169") (name "TX5") (class "Default")
      (node (ref "IC12") (pin "27") (pinfunction "IO16_27") (pintype "bidirectional"))
      (node (ref "J18") (pin "3") (pinfunction "3_3") (pintype "passive"))
      (node (ref "ST1") (pin "31") (pinfunction "TX5_31") (pintype "output"))
    )
    (net (code "170") (name "TX6") (class "Default")
      (node (ref "J19") (pin "3") (pinfunction "3_3") (pintype "passive"))
      (node (ref "ST1") (pin "33") (pinfunction "TX6_33") (pintype "output"))
    )
    (net (code "171") (name "TXD0") (class "Default")
      (node (ref "IC12") (pin "35") (pinfunction "TXD0_35") (pintype "bidirectional"))
      (node (ref "J25") (pin "2") (pinfunction "2_2") (pintype "passive"))
    )
    (net (code "172") (name "unconnected-(IC8-~{INT}-Pad13)") (class "Default")
      (node (ref "IC8") (pin "13") (pinfunction "~{INT}_13") (pintype "output"))
    )
    (net (code "173") (name "unconnected-(IC10-PadVMM)") (class "Default")
      (node (ref "IC10") (pin "VMM") (pinfunction "VMM_VMM") (pintype "bidirectional"))
    )
    (net (code "174") (name "unconnected-(IC12-IO23-Pad37)") (class "Default")
      (node (ref "IC12") (pin "37") (pinfunction "IO23_37") (pintype "bidirectional"))
    )
    (net (code "175") (name "unconnected-(IC12-NC-Pad32)") (class "Default")
      (node (ref "IC12") (pin "32") (pinfunction "NC_32") (pintype "bidirectional"))
    )
    (net (code "176") (name "unconnected-(IC13-MUTE-Pad5)") (class "Default")
      (node (ref "IC13") (pin "5") (pinfunction "MUTE_5") (pintype "input"))
    )
    (net (code "177") (name "unconnected-(IC13-NC-Pad9)") (class "Default")
      (node (ref "IC13") (pin "9") (pinfunction "NC_9") (pintype "no_connect"))
    )
    (net (code "178") (name "unconnected-(J16-Pad2)") (class "Default")
      (node (ref "J16") (pin "2") (pinfunction "2_2") (pintype "passive"))
    )
    (net (code "179") (name "unconnected-(ST1-SPI2_CS0-Pad37)") (class "Default")
      (node (ref "ST1") (pin "37") (pinfunction "SPI2_CS0_37") (pintype "bidirectional"))
    )
    (net (code "180") (name "unconnected-(ST1-SPI2_CS1-Pad38)") (class "Default")
      (node (ref "ST1") (pin "38") (pinfunction "SPI2_CS1_38") (pintype "bidirectional"))
    )
    (net (code "181") (name "unconnected-(ST1-SPI2_MISO-Pad35)") (class "Default")
      (node (ref "ST1") (pin "35") (pinfunction "SPI2_MISO_35") (pintype "bidirectional"))
    )
    (net (code "182") (name "unconnected-(ST1-SPI2_MOSI-Pad34)") (class "Default")
      (node (ref "ST1") (pin "34") (pinfunction "SPI2_MOSI_34") (pintype "bidirectional"))
    )
    (net (code "183") (name "unconnected-(ST1-SPI2_SCK-Pad36)") (class "Default")
      (node (ref "ST1") (pin "36") (pinfunction "SPI2_SCK_36") (pintype "bidirectional"))
    )
    (net (code "184") (name "unconnected-(ST3-Pad5)") (class "Default")
      (node (ref "ST3") (pin "5") (pinfunction "5_5") (pintype "passive"))
    )
    (net (code "185") (name "unconnected-(SW1-S-Pad3)") (class "Default")
      (node (ref "SW1") (pin "3") (pinfunction "S_3") (pintype "passive"))
    )
  )
)
